# untitled.net
KiCad netlist of a schematic drawn in EAGLE
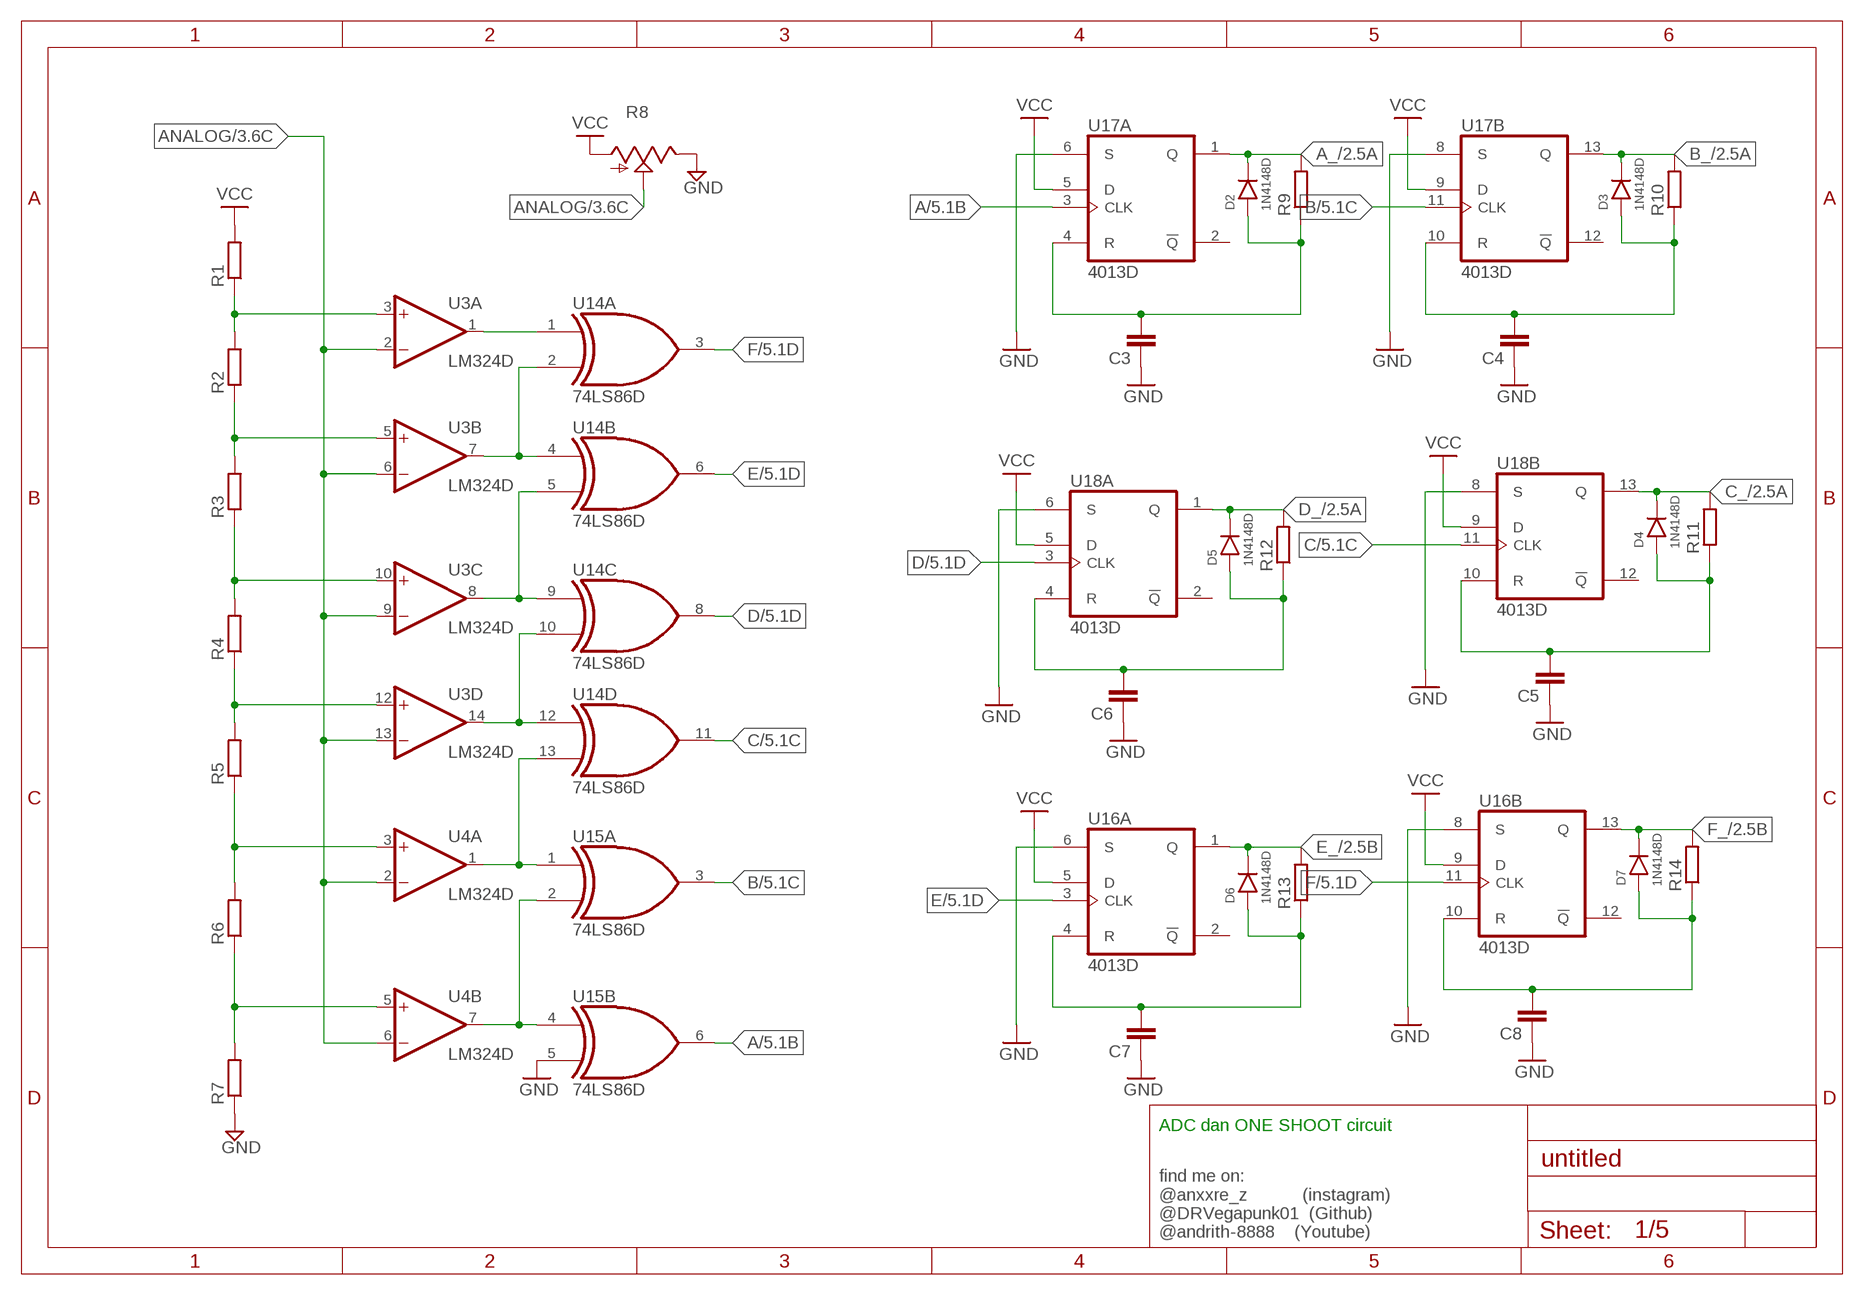
[diagram p0: schematic, sheet 1]
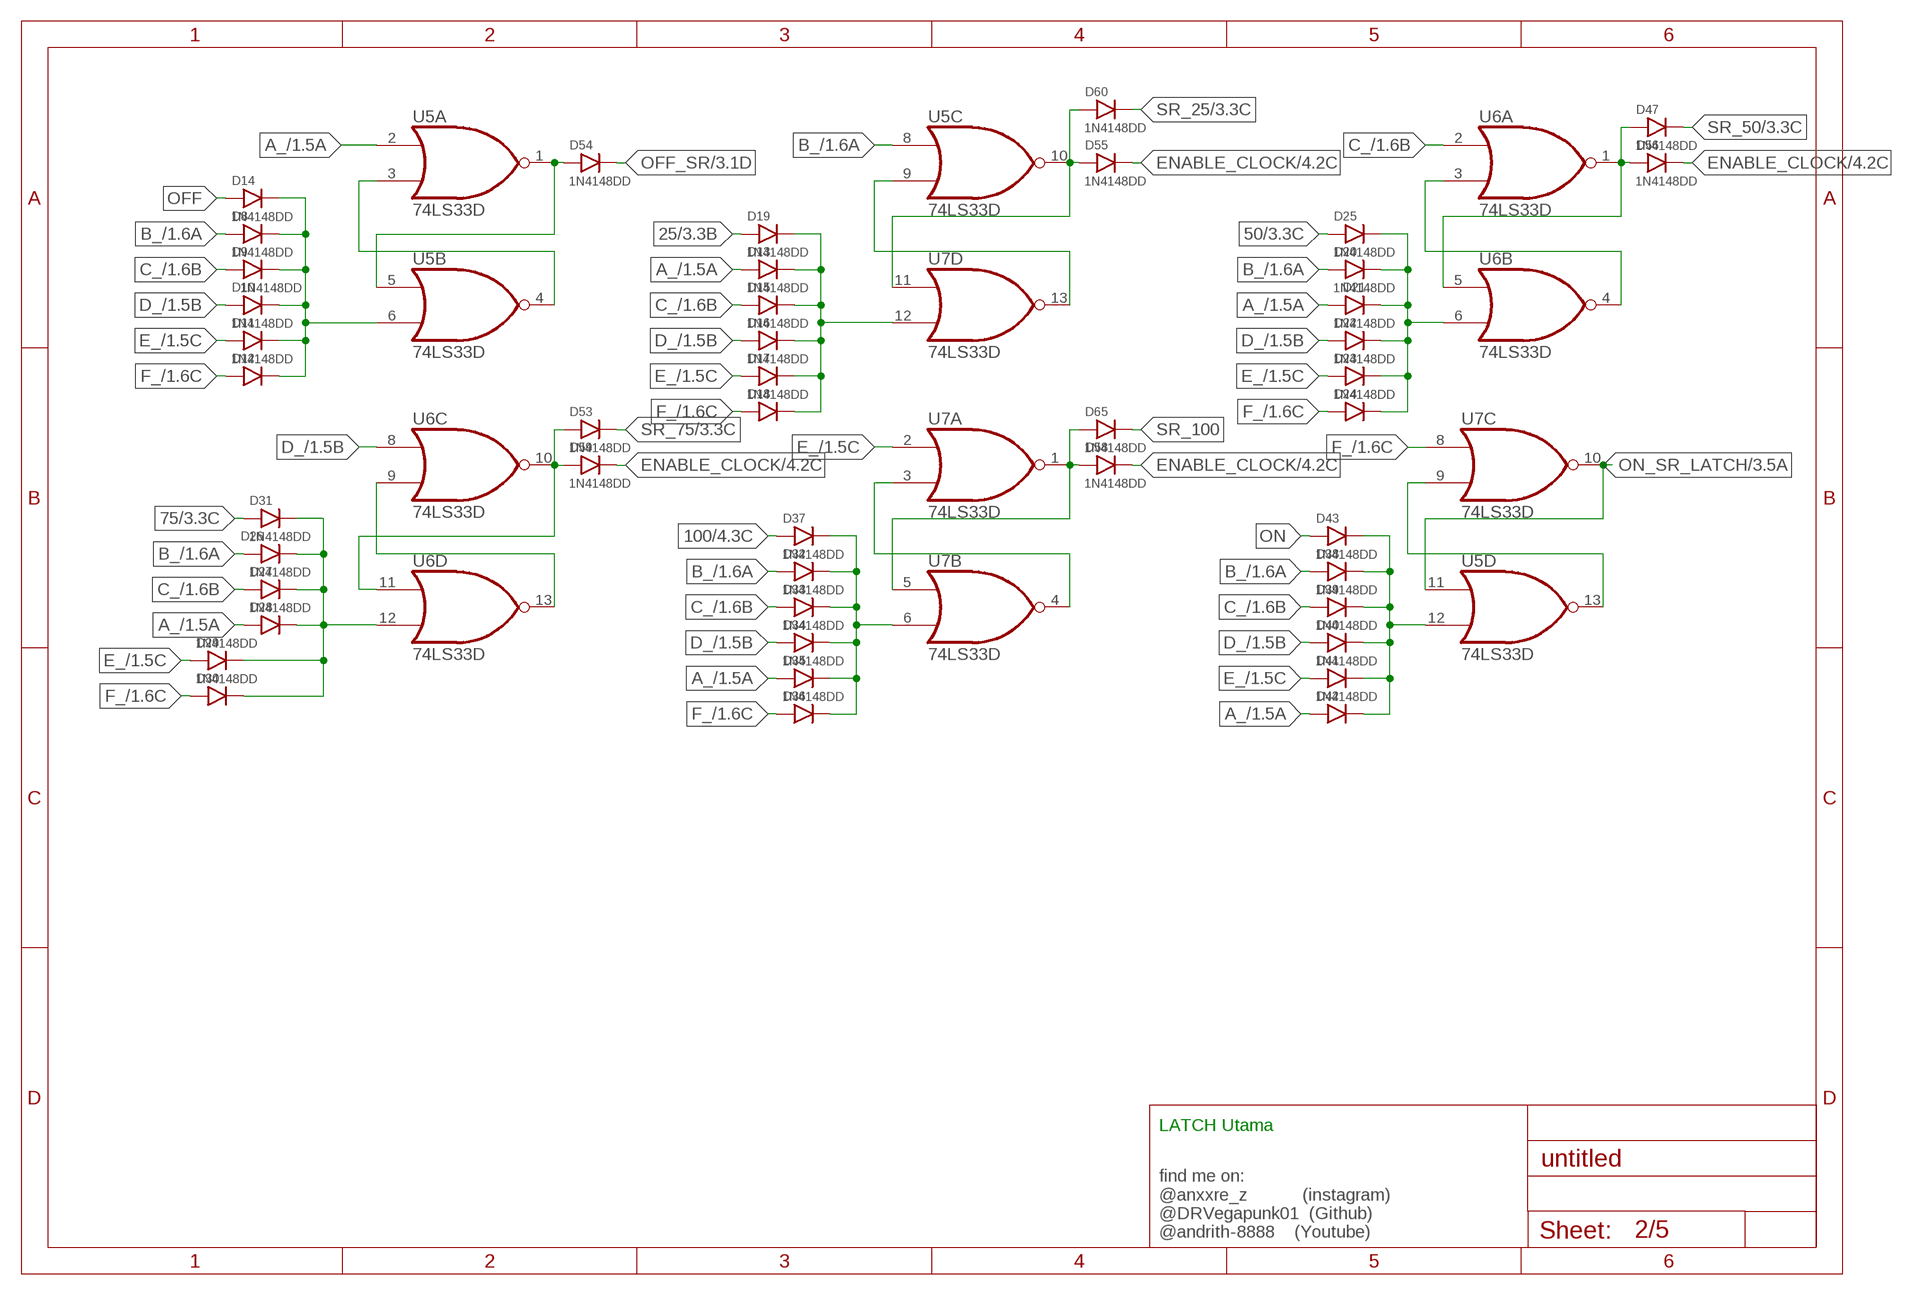
[diagram p1: schematic, sheet 2]
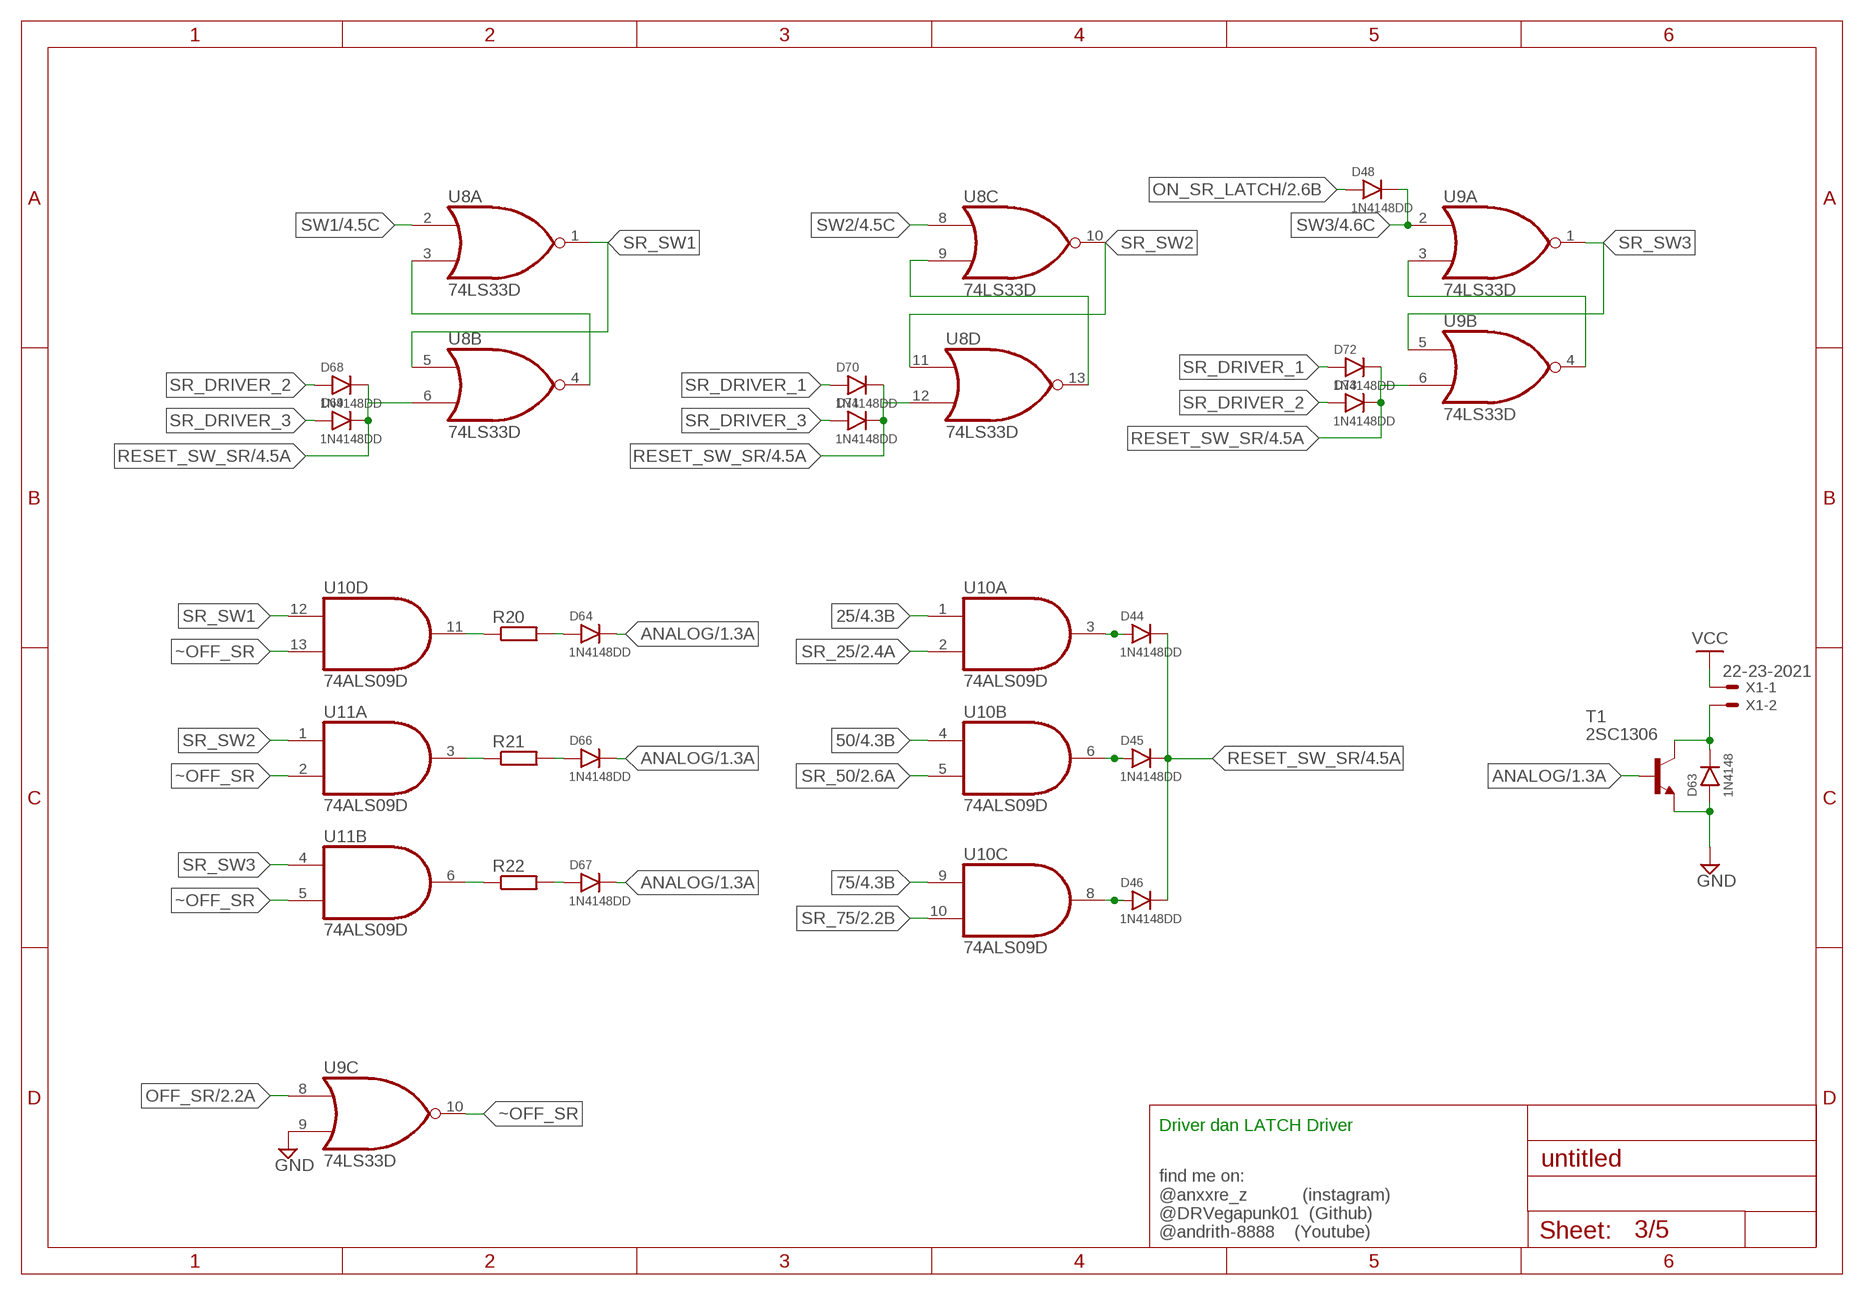
[diagram p2: schematic, sheet 3]
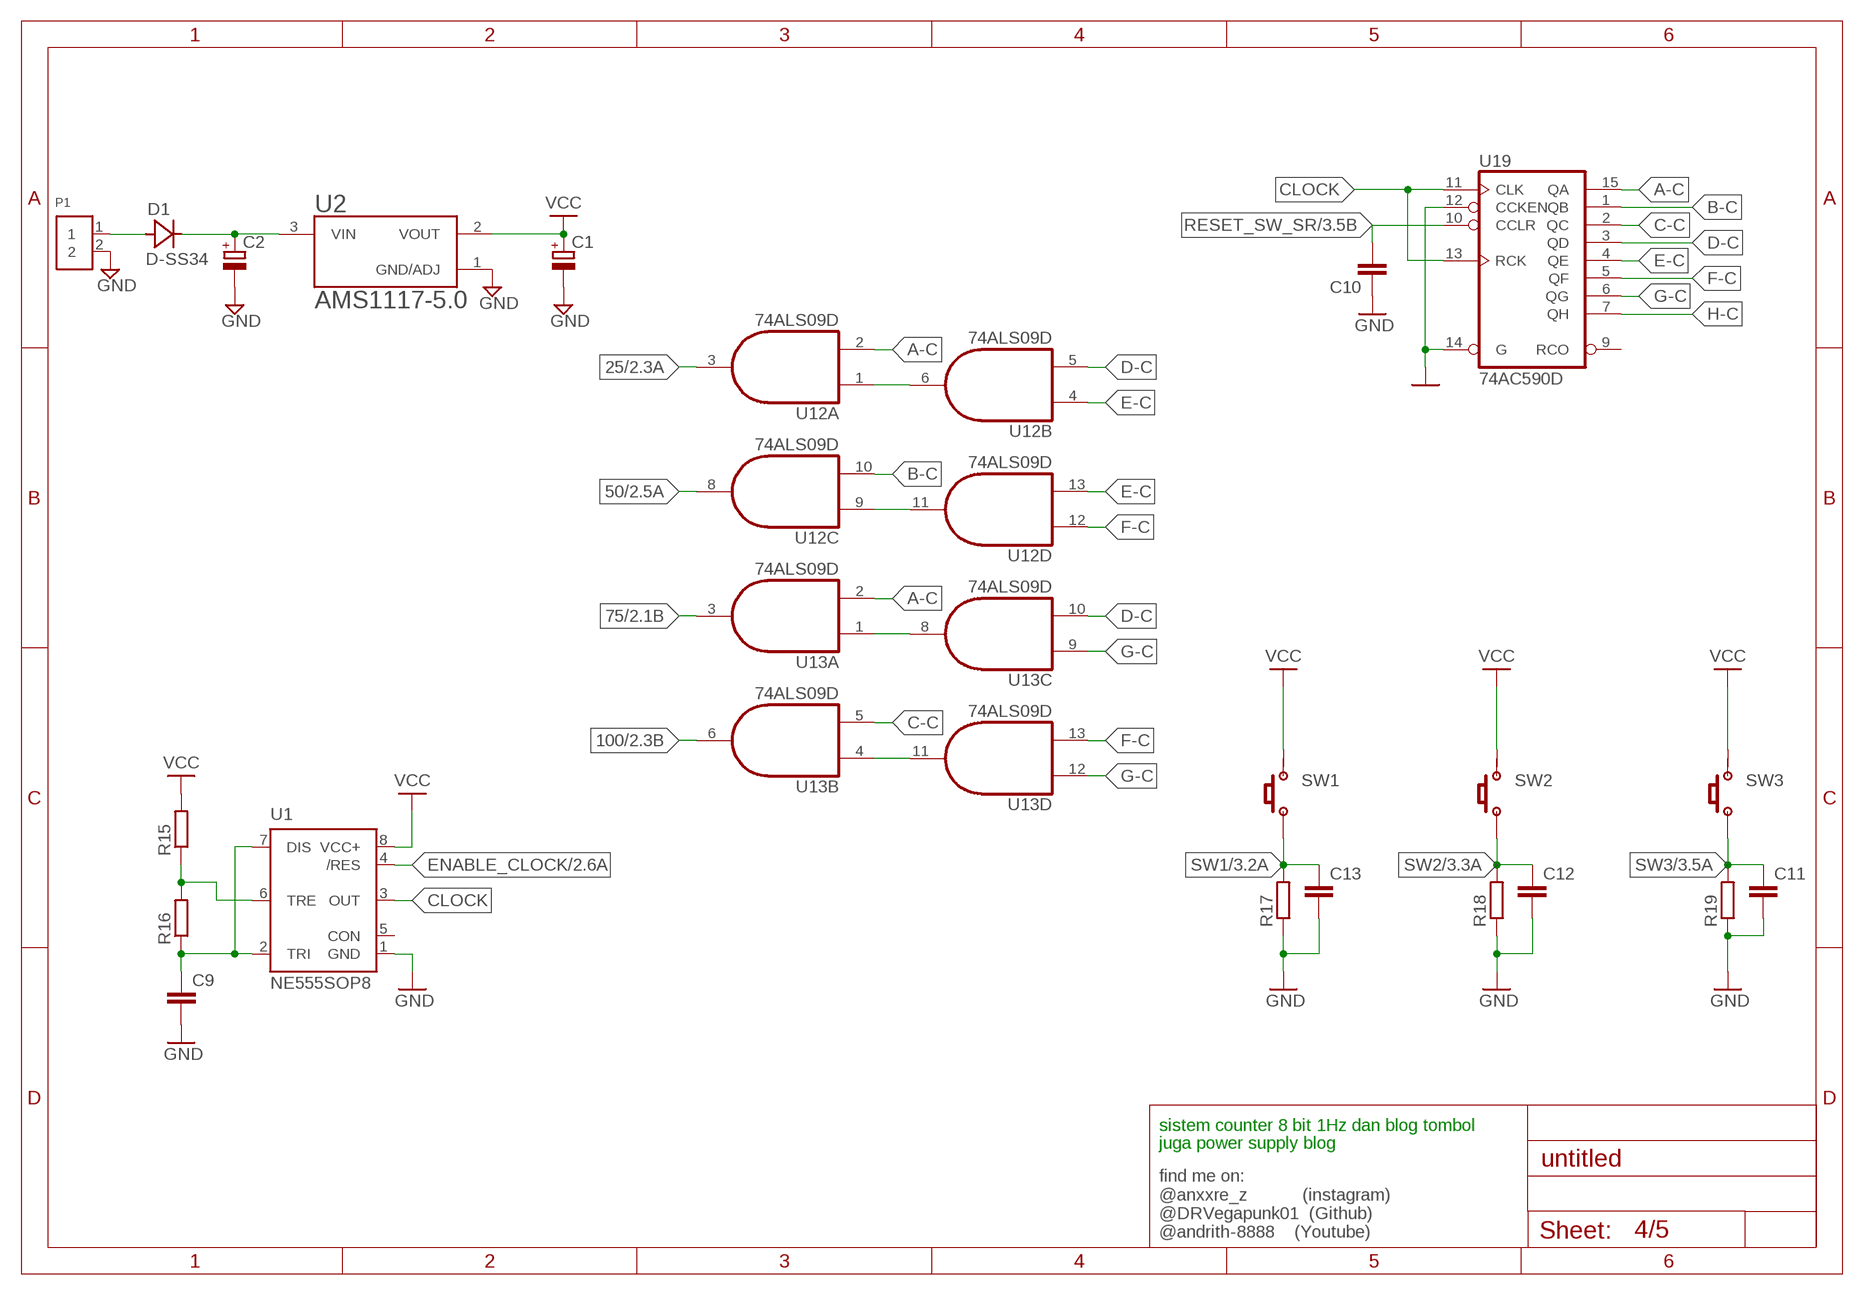
[diagram p3: schematic, sheet 4]
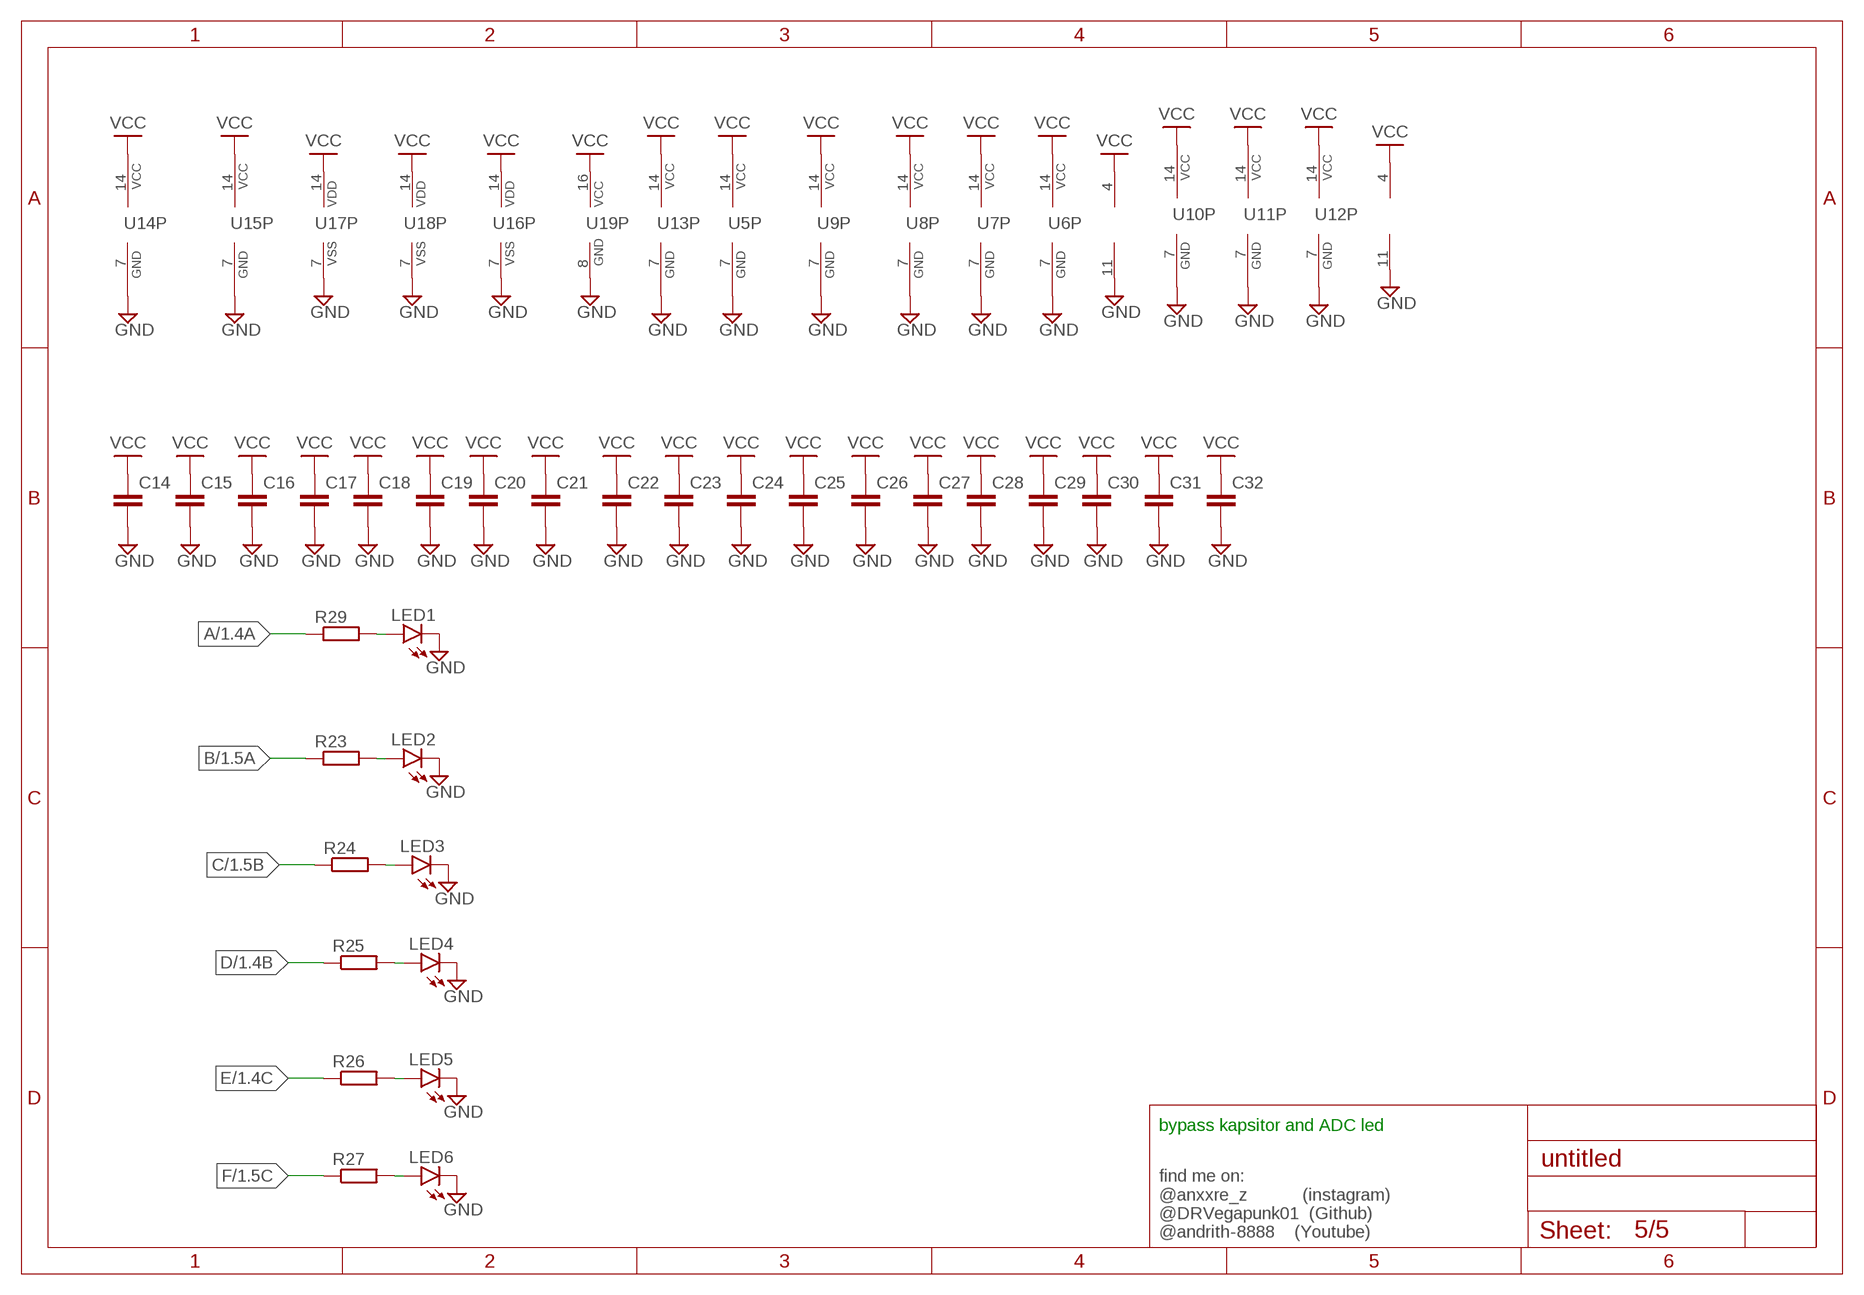
[diagram p4: schematic, sheet 5]

(export (version "E")
  (design (tool "Eeschema 10.0.6"))
  (components
    (comp (ref "D8")
      (value "1N4148DD")
      (footprint "eagle-import:SOD123")
      (libsource (lib "eagle-import") (part "1N4148DD"))
    )
    (comp (ref "D9")
      (value "1N4148DD")
      (footprint "eagle-import:SOD123")
      (libsource (lib "eagle-import") (part "1N4148DD"))
    )
    (comp (ref "D10")
      (value "1N4148DD")
      (footprint "eagle-import:SOD123")
      (libsource (lib "eagle-import") (part "1N4148DD"))
    )
    (comp (ref "D11")
      (value "1N4148DD")
      (footprint "eagle-import:SOD123")
      (libsource (lib "eagle-import") (part "1N4148DD"))
    )
    (comp (ref "D12")
      (value "1N4148DD")
      (footprint "eagle-import:SOD123")
      (libsource (lib "eagle-import") (part "1N4148DD"))
    )
    (comp (ref "D13")
      (value "1N4148DD")
      (footprint "eagle-import:SOD123")
      (libsource (lib "eagle-import") (part "1N4148DD"))
    )
    (comp (ref "D14")
      (value "1N4148DD")
      (footprint "eagle-import:SOD123")
      (libsource (lib "eagle-import") (part "1N4148DD"))
    )
    (comp (ref "D15")
      (value "1N4148DD")
      (footprint "eagle-import:SOD123")
      (libsource (lib "eagle-import") (part "1N4148DD"))
    )
    (comp (ref "D16")
      (value "1N4148DD")
      (footprint "eagle-import:SOD123")
      (libsource (lib "eagle-import") (part "1N4148DD"))
    )
    (comp (ref "D17")
      (value "1N4148DD")
      (footprint "eagle-import:SOD123")
      (libsource (lib "eagle-import") (part "1N4148DD"))
    )
    (comp (ref "D18")
      (value "1N4148DD")
      (footprint "eagle-import:SOD123")
      (libsource (lib "eagle-import") (part "1N4148DD"))
    )
    (comp (ref "D19")
      (value "1N4148DD")
      (footprint "eagle-import:SOD123")
      (libsource (lib "eagle-import") (part "1N4148DD"))
    )
    (comp (ref "D20")
      (value "1N4148DD")
      (footprint "eagle-import:SOD123")
      (libsource (lib "eagle-import") (part "1N4148DD"))
    )
    (comp (ref "D21")
      (value "1N4148DD")
      (footprint "eagle-import:SOD123")
      (libsource (lib "eagle-import") (part "1N4148DD"))
    )
    (comp (ref "D22")
      (value "1N4148DD")
      (footprint "eagle-import:SOD123")
      (libsource (lib "eagle-import") (part "1N4148DD"))
    )
    (comp (ref "D23")
      (value "1N4148DD")
      (footprint "eagle-import:SOD123")
      (libsource (lib "eagle-import") (part "1N4148DD"))
    )
    (comp (ref "D24")
      (value "1N4148DD")
      (footprint "eagle-import:SOD123")
      (libsource (lib "eagle-import") (part "1N4148DD"))
    )
    (comp (ref "D25")
      (value "1N4148DD")
      (footprint "eagle-import:SOD123")
      (libsource (lib "eagle-import") (part "1N4148DD"))
    )
    (comp (ref "D26")
      (value "1N4148DD")
      (footprint "eagle-import:SOD123")
      (libsource (lib "eagle-import") (part "1N4148DD"))
    )
    (comp (ref "D27")
      (value "1N4148DD")
      (footprint "eagle-import:SOD123")
      (libsource (lib "eagle-import") (part "1N4148DD"))
    )
    (comp (ref "D28")
      (value "1N4148DD")
      (footprint "eagle-import:SOD123")
      (libsource (lib "eagle-import") (part "1N4148DD"))
    )
    (comp (ref "D29")
      (value "1N4148DD")
      (footprint "eagle-import:SOD123")
      (libsource (lib "eagle-import") (part "1N4148DD"))
    )
    (comp (ref "D30")
      (value "1N4148DD")
      (footprint "eagle-import:SOD123")
      (libsource (lib "eagle-import") (part "1N4148DD"))
    )
    (comp (ref "D31")
      (value "1N4148DD")
      (footprint "eagle-import:SOD123")
      (libsource (lib "eagle-import") (part "1N4148DD"))
    )
    (comp (ref "D32")
      (value "1N4148DD")
      (footprint "eagle-import:SOD123")
      (libsource (lib "eagle-import") (part "1N4148DD"))
    )
    (comp (ref "D33")
      (value "1N4148DD")
      (footprint "eagle-import:SOD123")
      (libsource (lib "eagle-import") (part "1N4148DD"))
    )
    (comp (ref "D34")
      (value "1N4148DD")
      (footprint "eagle-import:SOD123")
      (libsource (lib "eagle-import") (part "1N4148DD"))
    )
    (comp (ref "D35")
      (value "1N4148DD")
      (footprint "eagle-import:SOD123")
      (libsource (lib "eagle-import") (part "1N4148DD"))
    )
    (comp (ref "D36")
      (value "1N4148DD")
      (footprint "eagle-import:SOD123")
      (libsource (lib "eagle-import") (part "1N4148DD"))
    )
    (comp (ref "D37")
      (value "1N4148DD")
      (footprint "eagle-import:SOD123")
      (libsource (lib "eagle-import") (part "1N4148DD"))
    )
    (comp (ref "D38")
      (value "1N4148DD")
      (footprint "eagle-import:SOD123")
      (libsource (lib "eagle-import") (part "1N4148DD"))
    )
    (comp (ref "D39")
      (value "1N4148DD")
      (footprint "eagle-import:SOD123")
      (libsource (lib "eagle-import") (part "1N4148DD"))
    )
    (comp (ref "D40")
      (value "1N4148DD")
      (footprint "eagle-import:SOD123")
      (libsource (lib "eagle-import") (part "1N4148DD"))
    )
    (comp (ref "D41")
      (value "1N4148DD")
      (footprint "eagle-import:SOD123")
      (libsource (lib "eagle-import") (part "1N4148DD"))
    )
    (comp (ref "D42")
      (value "1N4148DD")
      (footprint "eagle-import:SOD123")
      (libsource (lib "eagle-import") (part "1N4148DD"))
    )
    (comp (ref "D43")
      (value "1N4148DD")
      (footprint "eagle-import:SOD123")
      (libsource (lib "eagle-import") (part "1N4148DD"))
    )
    (comp (ref "D47")
      (value "1N4148DD")
      (footprint "eagle-import:SOD123")
      (libsource (lib "eagle-import") (part "1N4148DD"))
    )
    (comp (ref "D53")
      (value "1N4148DD")
      (footprint "eagle-import:SOD123")
      (libsource (lib "eagle-import") (part "1N4148DD"))
    )
    (comp (ref "D54")
      (value "1N4148DD")
      (footprint "eagle-import:SOD123")
      (libsource (lib "eagle-import") (part "1N4148DD"))
    )
    (comp (ref "D55")
      (value "1N4148DD")
      (footprint "eagle-import:SOD123")
      (libsource (lib "eagle-import") (part "1N4148DD"))
    )
    (comp (ref "D56")
      (value "1N4148DD")
      (footprint "eagle-import:SOD123")
      (libsource (lib "eagle-import") (part "1N4148DD"))
    )
    (comp (ref "D58")
      (value "1N4148DD")
      (footprint "eagle-import:SOD123")
      (libsource (lib "eagle-import") (part "1N4148DD"))
    )
    (comp (ref "D59")
      (value "1N4148DD")
      (footprint "eagle-import:SOD123")
      (libsource (lib "eagle-import") (part "1N4148DD"))
    )
    (comp (ref "D60")
      (value "1N4148DD")
      (footprint "eagle-import:SOD123")
      (libsource (lib "eagle-import") (part "1N4148DD"))
    )
    (comp (ref "D65")
      (value "1N4148DD")
      (footprint "eagle-import:SOD123")
      (libsource (lib "eagle-import") (part "1N4148DD"))
    )
    (comp (ref "U5")
      (value "74LS33D")
      (footprint "eagle-import:SO14")
      (libsource (lib "eagle-import") (part "7433DLS"))
    )
    (comp (ref "U6")
      (value "74LS33D")
      (footprint "eagle-import:SO14")
      (libsource (lib "eagle-import") (part "7433DLS"))
    )
    (comp (ref "U7")
      (value "74LS33D")
      (footprint "eagle-import:SO14")
      (libsource (lib "eagle-import") (part "7433DLS"))
    )
    (comp (ref "D44")
      (value "1N4148DD")
      (footprint "eagle-import:SOD123")
      (libsource (lib "eagle-import") (part "1N4148DD"))
    )
    (comp (ref "D45")
      (value "1N4148DD")
      (footprint "eagle-import:SOD123")
      (libsource (lib "eagle-import") (part "1N4148DD"))
    )
    (comp (ref "D46")
      (value "1N4148DD")
      (footprint "eagle-import:SOD123")
      (libsource (lib "eagle-import") (part "1N4148DD"))
    )
    (comp (ref "D48")
      (value "1N4148DD")
      (footprint "eagle-import:SOD123")
      (libsource (lib "eagle-import") (part "1N4148DD"))
    )
    (comp (ref "D63")
      (value "1N4148")
      (footprint "eagle-import:DIODE")
      (libsource (lib "eagle-import") (part "1N4148"))
    )
    (comp (ref "D64")
      (value "1N4148DD")
      (footprint "eagle-import:SOD123")
      (libsource (lib "eagle-import") (part "1N4148DD"))
    )
    (comp (ref "D66")
      (value "1N4148DD")
      (footprint "eagle-import:SOD123")
      (libsource (lib "eagle-import") (part "1N4148DD"))
    )
    (comp (ref "D67")
      (value "1N4148DD")
      (footprint "eagle-import:SOD123")
      (libsource (lib "eagle-import") (part "1N4148DD"))
    )
    (comp (ref "D68")
      (value "1N4148DD")
      (footprint "eagle-import:SOD123")
      (libsource (lib "eagle-import") (part "1N4148DD"))
    )
    (comp (ref "D69")
      (value "1N4148DD")
      (footprint "eagle-import:SOD123")
      (libsource (lib "eagle-import") (part "1N4148DD"))
    )
    (comp (ref "D70")
      (value "1N4148DD")
      (footprint "eagle-import:SOD123")
      (libsource (lib "eagle-import") (part "1N4148DD"))
    )
    (comp (ref "D71")
      (value "1N4148DD")
      (footprint "eagle-import:SOD123")
      (libsource (lib "eagle-import") (part "1N4148DD"))
    )
    (comp (ref "D72")
      (value "1N4148DD")
      (footprint "eagle-import:SOD123")
      (libsource (lib "eagle-import") (part "1N4148DD"))
    )
    (comp (ref "D73")
      (value "1N4148DD")
      (footprint "eagle-import:SOD123")
      (libsource (lib "eagle-import") (part "1N4148DD"))
    )
    (comp (ref "R20")
      (value "RES0805")
      (footprint "eagle-import:SMD0805")
      (libsource (lib "eagle-import") (part "RES0805"))
    )
    (comp (ref "R21")
      (value "RES0805")
      (footprint "eagle-import:SMD0805")
      (libsource (lib "eagle-import") (part "RES0805"))
    )
    (comp (ref "R22")
      (value "RES0805")
      (footprint "eagle-import:SMD0805")
      (libsource (lib "eagle-import") (part "RES0805"))
    )
    (comp (ref "T1")
      (value "2SC1306")
      (footprint "eagle-import:TO220BV")
      (libsource (lib "eagle-import") (part "2SC1306"))
    )
    (comp (ref "U8")
      (value "74LS33D")
      (footprint "eagle-import:SO14")
      (libsource (lib "eagle-import") (part "7433DLS"))
    )
    (comp (ref "U9")
      (value "74LS33D")
      (footprint "eagle-import:SO14")
      (libsource (lib "eagle-import") (part "7433DLS"))
    )
    (comp (ref "U10")
      (value "74ALS09D")
      (footprint "eagle-import:SO14")
      (libsource (lib "eagle-import") (part "7409DALS"))
    )
    (comp (ref "U11")
      (value "74ALS09D")
      (footprint "eagle-import:SO14")
      (libsource (lib "eagle-import") (part "7409DALS"))
    )
    (comp (ref "X1")
      (value "22-23-2021")
      (footprint "eagle-import:22-23-2021")
      (fields (field (name "MF") "MOLEX"))
      (libsource (lib "eagle-import") (part "22-23-2021"))
    )
    (comp (ref "C14")
      (value "CAP-NON0805")
      (footprint "eagle-import:SMD0805")
      (libsource (lib "eagle-import") (part "CAP-NON0805"))
    )
    (comp (ref "C15")
      (value "CAP-NON0805")
      (footprint "eagle-import:SMD0805")
      (libsource (lib "eagle-import") (part "CAP-NON0805"))
    )
    (comp (ref "C16")
      (value "CAP-NON0805")
      (footprint "eagle-import:SMD0805")
      (libsource (lib "eagle-import") (part "CAP-NON0805"))
    )
    (comp (ref "C17")
      (value "CAP-NON0805")
      (footprint "eagle-import:SMD0805")
      (libsource (lib "eagle-import") (part "CAP-NON0805"))
    )
    (comp (ref "C18")
      (value "CAP-NON0805")
      (footprint "eagle-import:SMD0805")
      (libsource (lib "eagle-import") (part "CAP-NON0805"))
    )
    (comp (ref "C19")
      (value "CAP-NON0805")
      (footprint "eagle-import:SMD0805")
      (libsource (lib "eagle-import") (part "CAP-NON0805"))
    )
    (comp (ref "C20")
      (value "CAP-NON0805")
      (footprint "eagle-import:SMD0805")
      (libsource (lib "eagle-import") (part "CAP-NON0805"))
    )
    (comp (ref "C21")
      (value "CAP-NON0805")
      (footprint "eagle-import:SMD0805")
      (libsource (lib "eagle-import") (part "CAP-NON0805"))
    )
    (comp (ref "C22")
      (value "CAP-NON0805")
      (footprint "eagle-import:SMD0805")
      (libsource (lib "eagle-import") (part "CAP-NON0805"))
    )
    (comp (ref "C23")
      (value "CAP-NON0805")
      (footprint "eagle-import:SMD0805")
      (libsource (lib "eagle-import") (part "CAP-NON0805"))
    )
    (comp (ref "C24")
      (value "CAP-NON0805")
      (footprint "eagle-import:SMD0805")
      (libsource (lib "eagle-import") (part "CAP-NON0805"))
    )
    (comp (ref "C25")
      (value "CAP-NON0805")
      (footprint "eagle-import:SMD0805")
      (libsource (lib "eagle-import") (part "CAP-NON0805"))
    )
    (comp (ref "C26")
      (value "CAP-NON0805")
      (footprint "eagle-import:SMD0805")
      (libsource (lib "eagle-import") (part "CAP-NON0805"))
    )
    (comp (ref "C27")
      (value "CAP-NON0805")
      (footprint "eagle-import:SMD0805")
      (libsource (lib "eagle-import") (part "CAP-NON0805"))
    )
    (comp (ref "C28")
      (value "CAP-NON0805")
      (footprint "eagle-import:SMD0805")
      (libsource (lib "eagle-import") (part "CAP-NON0805"))
    )
    (comp (ref "C29")
      (value "CAP-NON0805")
      (footprint "eagle-import:SMD0805")
      (libsource (lib "eagle-import") (part "CAP-NON0805"))
    )
    (comp (ref "C30")
      (value "CAP-NON0805")
      (footprint "eagle-import:SMD0805")
      (libsource (lib "eagle-import") (part "CAP-NON0805"))
    )
    (comp (ref "C31")
      (value "CAP-NON0805")
      (footprint "eagle-import:SMD0805")
      (libsource (lib "eagle-import") (part "CAP-NON0805"))
    )
    (comp (ref "C32")
      (value "CAP-NON0805")
      (footprint "eagle-import:SMD0805")
      (libsource (lib "eagle-import") (part "CAP-NON0805"))
    )
    (comp (ref "LED1")
      (value "LED0805")
      (footprint "eagle-import:CHIPLED_0805")
      (libsource (lib "eagle-import") (part "LED0805"))
    )
    (comp (ref "LED2")
      (value "LED0805")
      (footprint "eagle-import:CHIPLED_0805")
      (libsource (lib "eagle-import") (part "LED0805"))
    )
    (comp (ref "LED3")
      (value "LED0805")
      (footprint "eagle-import:CHIPLED_0805")
      (libsource (lib "eagle-import") (part "LED0805"))
    )
    (comp (ref "LED4")
      (value "LED0805")
      (footprint "eagle-import:CHIPLED_0805")
      (libsource (lib "eagle-import") (part "LED0805"))
    )
    (comp (ref "LED5")
      (value "LED0805")
      (footprint "eagle-import:CHIPLED_0805")
      (libsource (lib "eagle-import") (part "LED0805"))
    )
    (comp (ref "LED6")
      (value "LED0805")
      (footprint "eagle-import:CHIPLED_0805")
      (libsource (lib "eagle-import") (part "LED0805"))
    )
    (comp (ref "R23")
      (value "RES0805")
      (footprint "eagle-import:SMD0805")
      (libsource (lib "eagle-import") (part "RES0805"))
    )
    (comp (ref "R24")
      (value "RES0805")
      (footprint "eagle-import:SMD0805")
      (libsource (lib "eagle-import") (part "RES0805"))
    )
    (comp (ref "R25")
      (value "RES0805")
      (footprint "eagle-import:SMD0805")
      (libsource (lib "eagle-import") (part "RES0805"))
    )
    (comp (ref "R26")
      (value "RES0805")
      (footprint "eagle-import:SMD0805")
      (libsource (lib "eagle-import") (part "RES0805"))
    )
    (comp (ref "R27")
      (value "RES0805")
      (footprint "eagle-import:SMD0805")
      (libsource (lib "eagle-import") (part "RES0805"))
    )
    (comp (ref "R29")
      (value "RES0805")
      (footprint "eagle-import:SMD0805")
      (libsource (lib "eagle-import") (part "RES0805"))
    )
    (comp (ref "U3")
      (value "LM324D")
      (footprint "eagle-import:SO14")
      (libsource (lib "eagle-import") (part "LM324D"))
    )
    (comp (ref "U4")
      (value "LM324D")
      (footprint "eagle-import:SO14")
      (libsource (lib "eagle-import") (part "LM324D"))
    )
    (comp (ref "U12")
      (value "74ALS09D")
      (footprint "eagle-import:SO14")
      (libsource (lib "eagle-import") (part "7409DALS"))
    )
    (comp (ref "U13")
      (value "74ALS09D")
      (footprint "eagle-import:SO14")
      (libsource (lib "eagle-import") (part "7409DALS"))
    )
    (comp (ref "U14")
      (value "74LS86D")
      (footprint "eagle-import:SO14")
      (libsource (lib "eagle-import") (part "7486DLS"))
    )
    (comp (ref "U15")
      (value "74LS86D")
      (footprint "eagle-import:SO14")
      (libsource (lib "eagle-import") (part "7486DLS"))
    )
    (comp (ref "U16")
      (value "4013D")
      (footprint "eagle-import:SO14")
      (libsource (lib "eagle-import") (part "4013D"))
    )
    (comp (ref "U17")
      (value "4013D")
      (footprint "eagle-import:SO14")
      (libsource (lib "eagle-import") (part "4013D"))
    )
    (comp (ref "U18")
      (value "4013D")
      (footprint "eagle-import:SO14")
      (libsource (lib "eagle-import") (part "4013D"))
    )
    (comp (ref "U19")
      (value "74AC590D")
      (footprint "eagle-import:SO16")
      (libsource (lib "eagle-import") (part "74590DAC"))
    )
    (comp (ref "C1")
      (value "CAP-POLARE5-4")
      (footprint "eagle-import:E5-4")
      (libsource (lib "eagle-import") (part "CAP-POLARE5-4"))
    )
    (comp (ref "C2")
      (value "CAP-POLARE5-4")
      (footprint "eagle-import:E5-4")
      (libsource (lib "eagle-import") (part "CAP-POLARE5-4"))
    )
    (comp (ref "C9")
      (value "CAP-NON0805")
      (footprint "eagle-import:SMD0805")
      (libsource (lib "eagle-import") (part "CAP-NON0805"))
    )
    (comp (ref "C10")
      (value "CAP-NON0805")
      (footprint "eagle-import:SMD0805")
      (libsource (lib "eagle-import") (part "CAP-NON0805"))
    )
    (comp (ref "C11")
      (value "CAP-NON0805")
      (footprint "eagle-import:SMD0805")
      (libsource (lib "eagle-import") (part "CAP-NON0805"))
    )
    (comp (ref "C12")
      (value "CAP-NON0805")
      (footprint "eagle-import:SMD0805")
      (libsource (lib "eagle-import") (part "CAP-NON0805"))
    )
    (comp (ref "C13")
      (value "CAP-NON0805")
      (footprint "eagle-import:SMD0805")
      (libsource (lib "eagle-import") (part "CAP-NON0805"))
    )
    (comp (ref "D1")
      (value "D-SS34")
      (footprint "eagle-import:SMA")
      (libsource (lib "eagle-import") (part "D-SS34"))
    )
    (comp (ref "P1")
      (value "TERMINALBLOK")
      (footprint "eagle-import:TB-2P")
      (libsource (lib "eagle-import") (part "TERMINALBLOK"))
    )
    (comp (ref "R15")
      (value "RES0805")
      (footprint "eagle-import:SMD0805")
      (libsource (lib "eagle-import") (part "RES0805"))
    )
    (comp (ref "R16")
      (value "RES0805")
      (footprint "eagle-import:SMD0805")
      (libsource (lib "eagle-import") (part "RES0805"))
    )
    (comp (ref "R17")
      (value "RES0805")
      (footprint "eagle-import:SMD0805")
      (libsource (lib "eagle-import") (part "RES0805"))
    )
    (comp (ref "R18")
      (value "RES0805")
      (footprint "eagle-import:SMD0805")
      (libsource (lib "eagle-import") (part "RES0805"))
    )
    (comp (ref "R19")
      (value "RES0805")
      (footprint "eagle-import:SMD0805")
      (libsource (lib "eagle-import") (part "RES0805"))
    )
    (comp (ref "SW1")
      (value "PUSH_BUTTON4P")
      (footprint "eagle-import:PUSH_BUTTON_4P")
      (libsource (lib "eagle-import") (part "PUSH_BUTTON4P"))
    )
    (comp (ref "SW2")
      (value "PUSH_BUTTON4P")
      (footprint "eagle-import:PUSH_BUTTON_4P")
      (libsource (lib "eagle-import") (part "PUSH_BUTTON4P"))
    )
    (comp (ref "SW3")
      (value "PUSH_BUTTON4P")
      (footprint "eagle-import:PUSH_BUTTON_4P")
      (libsource (lib "eagle-import") (part "PUSH_BUTTON4P"))
    )
    (comp (ref "U1")
      (value "NE555SOP8")
      (footprint "eagle-import:SO08")
      (libsource (lib "eagle-import") (part "NE555SOP8"))
    )
    (comp (ref "U2")
      (value "AMS1117-5.0")
      (footprint "eagle-import:SOT229P700X180-4N")
      (libsource (lib "eagle-import") (part "AMS1117-5.0"))
    )
    (comp (ref "C3")
      (value "CAP-NON0805")
      (footprint "eagle-import:SMD0805")
      (libsource (lib "eagle-import") (part "CAP-NON0805"))
    )
    (comp (ref "C4")
      (value "CAP-NON0805")
      (footprint "eagle-import:SMD0805")
      (libsource (lib "eagle-import") (part "CAP-NON0805"))
    )
    (comp (ref "C5")
      (value "CAP-NON0805")
      (footprint "eagle-import:SMD0805")
      (libsource (lib "eagle-import") (part "CAP-NON0805"))
    )
    (comp (ref "C6")
      (value "CAP-NON0805")
      (footprint "eagle-import:SMD0805")
      (libsource (lib "eagle-import") (part "CAP-NON0805"))
    )
    (comp (ref "C7")
      (value "CAP-NON0805")
      (footprint "eagle-import:SMD0805")
      (libsource (lib "eagle-import") (part "CAP-NON0805"))
    )
    (comp (ref "C8")
      (value "CAP-NON0805")
      (footprint "eagle-import:SMD0805")
      (libsource (lib "eagle-import") (part "CAP-NON0805"))
    )
    (comp (ref "D2")
      (value "1N4148D")
      (footprint "eagle-import:SOD80C")
      (libsource (lib "eagle-import") (part "1N4148D"))
    )
    (comp (ref "D3")
      (value "1N4148D")
      (footprint "eagle-import:SOD80C")
      (libsource (lib "eagle-import") (part "1N4148D"))
    )
    (comp (ref "D4")
      (value "1N4148D")
      (footprint "eagle-import:SOD80C")
      (libsource (lib "eagle-import") (part "1N4148D"))
    )
    (comp (ref "D5")
      (value "1N4148D")
      (footprint "eagle-import:SOD80C")
      (libsource (lib "eagle-import") (part "1N4148D"))
    )
    (comp (ref "D6")
      (value "1N4148D")
      (footprint "eagle-import:SOD80C")
      (libsource (lib "eagle-import") (part "1N4148D"))
    )
    (comp (ref "D7")
      (value "1N4148D")
      (footprint "eagle-import:SOD80C")
      (libsource (lib "eagle-import") (part "1N4148D"))
    )
    (comp (ref "R1")
      (value "RES0805")
      (footprint "eagle-import:SMD0805")
      (libsource (lib "eagle-import") (part "RES0805"))
    )
    (comp (ref "R2")
      (value "RES0805")
      (footprint "eagle-import:SMD0805")
      (libsource (lib "eagle-import") (part "RES0805"))
    )
    (comp (ref "R3")
      (value "RES0805")
      (footprint "eagle-import:SMD0805")
      (libsource (lib "eagle-import") (part "RES0805"))
    )
    (comp (ref "R4")
      (value "RES0805")
      (footprint "eagle-import:SMD0805")
      (libsource (lib "eagle-import") (part "RES0805"))
    )
    (comp (ref "R5")
      (value "RES0805")
      (footprint "eagle-import:SMD0805")
      (libsource (lib "eagle-import") (part "RES0805"))
    )
    (comp (ref "R6")
      (value "RES0805")
      (footprint "eagle-import:SMD0805")
      (libsource (lib "eagle-import") (part "RES0805"))
    )
    (comp (ref "R7")
      (value "RES0805")
      (footprint "eagle-import:SMD0805")
      (libsource (lib "eagle-import") (part "RES0805"))
    )
    (comp (ref "R8")
      (value "TRIM_US-CT6")
      (footprint "eagle-import:CT6")
      (libsource (lib "eagle-import") (part "TRIM_US-CT6"))
    )
    (comp (ref "R9")
      (value "RES0805")
      (footprint "eagle-import:SMD0805")
      (libsource (lib "eagle-import") (part "RES0805"))
    )
    (comp (ref "R10")
      (value "RES0805")
      (footprint "eagle-import:SMD0805")
      (libsource (lib "eagle-import") (part "RES0805"))
    )
    (comp (ref "R11")
      (value "RES0805")
      (footprint "eagle-import:SMD0805")
      (libsource (lib "eagle-import") (part "RES0805"))
    )
    (comp (ref "R12")
      (value "RES0805")
      (footprint "eagle-import:SMD0805")
      (libsource (lib "eagle-import") (part "RES0805"))
    )
    (comp (ref "R13")
      (value "RES0805")
      (footprint "eagle-import:SMD0805")
      (libsource (lib "eagle-import") (part "RES0805"))
    )
    (comp (ref "R14")
      (value "RES0805")
      (footprint "eagle-import:SMD0805")
      (libsource (lib "eagle-import") (part "RES0805"))
    )
  )
  (nets
    (net (code "1") (name "25") (class "Default")
      (node (ref "D19") (pin "A") (pinfunction "1_A") (pintype "bidirectional"))
      (node (ref "U10") (pin "1") (pinfunction "I0_1") (pintype "input"))
      (node (ref "U12") (pin "3") (pinfunction "O_3") (pintype "open_collector"))
    )
    (net (code "2") (name "50") (class "Default")
      (node (ref "D25") (pin "A") (pinfunction "1_A") (pintype "bidirectional"))
      (node (ref "U10") (pin "4") (pinfunction "I0_4") (pintype "input"))
      (node (ref "U12") (pin "8") (pinfunction "O_8") (pintype "open_collector"))
    )
    (net (code "3") (name "75") (class "Default")
      (node (ref "D31") (pin "A") (pinfunction "1_A") (pintype "bidirectional"))
      (node (ref "U10") (pin "9") (pinfunction "I0_9") (pintype "input"))
      (node (ref "U13") (pin "3") (pinfunction "O_3") (pintype "open_collector"))
    )
    (net (code "4") (name "100") (class "Default")
      (node (ref "D37") (pin "A") (pinfunction "1_A") (pintype "bidirectional"))
      (node (ref "U13") (pin "6") (pinfunction "O_6") (pintype "open_collector"))
    )
    (net (code "5") (name "A") (class "Default")
      (node (ref "R29") (pin "1") (pinfunction "1_1") (pintype "passive"))
      (node (ref "U15") (pin "6") (pinfunction "O_6") (pintype "output"))
      (node (ref "U17") (pin "3") (pinfunction "CLK_3") (pintype "input"))
    )
    (net (code "6") (name "A-C") (class "Default")
      (node (ref "U12") (pin "2") (pinfunction "I1_2") (pintype "input"))
      (node (ref "U13") (pin "2") (pinfunction "I1_2") (pintype "input"))
      (node (ref "U19") (pin "15") (pinfunction "QA_15") (pintype "tri_state"))
    )
    (net (code "7") (name "ANALOG") (class "Default")
      (node (ref "D64") (pin "C") (pinfunction "2_C") (pintype "bidirectional"))
      (node (ref "D66") (pin "C") (pinfunction "2_C") (pintype "bidirectional"))
      (node (ref "D67") (pin "C") (pinfunction "2_C") (pintype "bidirectional"))
      (node (ref "R8") (pin "S") (pinfunction "S_S") (pintype "passive"))
      (node (ref "T1") (pin "1") (pinfunction "B_1") (pintype "passive"))
      (node (ref "U3") (pin "13") (pinfunction "-IN_13") (pintype "input"))
      (node (ref "U3") (pin "2") (pinfunction "-IN_2") (pintype "input"))
      (node (ref "U3") (pin "6") (pinfunction "-IN_6") (pintype "input"))
      (node (ref "U3") (pin "9") (pinfunction "-IN_9") (pintype "input"))
      (node (ref "U4") (pin "2") (pinfunction "-IN_2") (pintype "input"))
      (node (ref "U4") (pin "6") (pinfunction "-IN_6") (pintype "input"))
    )
    (net (code "8") (name "A_") (class "Default")
      (node (ref "D13") (pin "A") (pinfunction "1_A") (pintype "bidirectional"))
      (node (ref "D2") (pin "C") (pinfunction "2_C") (pintype "bidirectional"))
      (node (ref "D21") (pin "A") (pinfunction "1_A") (pintype "bidirectional"))
      (node (ref "D28") (pin "A") (pinfunction "1_A") (pintype "bidirectional"))
      (node (ref "D35") (pin "A") (pinfunction "1_A") (pintype "bidirectional"))
      (node (ref "D42") (pin "A") (pinfunction "1_A") (pintype "bidirectional"))
      (node (ref "R9") (pin "2") (pinfunction "2_2") (pintype "passive"))
      (node (ref "U17") (pin "1") (pinfunction "Q_1") (pintype "output"))
      (node (ref "U5") (pin "2") (pinfunction "I0_2") (pintype "input"))
    )
    (net (code "9") (name "B") (class "Default")
      (node (ref "R23") (pin "1") (pinfunction "1_1") (pintype "passive"))
      (node (ref "U15") (pin "3") (pinfunction "O_3") (pintype "output"))
      (node (ref "U17") (pin "11") (pinfunction "CLK_11") (pintype "input"))
    )
    (net (code "10") (name "B-C") (class "Default")
      (node (ref "U12") (pin "10") (pinfunction "I1_10") (pintype "input"))
      (node (ref "U19") (pin "1") (pinfunction "QB_1") (pintype "tri_state"))
    )
    (net (code "11") (name "B_") (class "Default")
      (node (ref "D20") (pin "A") (pinfunction "1_A") (pintype "bidirectional"))
      (node (ref "D26") (pin "A") (pinfunction "1_A") (pintype "bidirectional"))
      (node (ref "D3") (pin "C") (pinfunction "2_C") (pintype "bidirectional"))
      (node (ref "D32") (pin "A") (pinfunction "1_A") (pintype "bidirectional"))
      (node (ref "D38") (pin "A") (pinfunction "1_A") (pintype "bidirectional"))
      (node (ref "D8") (pin "A") (pinfunction "1_A") (pintype "bidirectional"))
      (node (ref "R10") (pin "2") (pinfunction "2_2") (pintype "passive"))
      (node (ref "U17") (pin "13") (pinfunction "Q_13") (pintype "output"))
      (node (ref "U5") (pin "8") (pinfunction "I0_8") (pintype "input"))
    )
    (net (code "12") (name "C") (class "Default")
      (node (ref "R24") (pin "1") (pinfunction "1_1") (pintype "passive"))
      (node (ref "U14") (pin "11") (pinfunction "O_11") (pintype "output"))
      (node (ref "U18") (pin "11") (pinfunction "CLK_11") (pintype "input"))
    )
    (net (code "13") (name "C-C") (class "Default")
      (node (ref "U13") (pin "5") (pinfunction "I1_5") (pintype "input"))
      (node (ref "U19") (pin "2") (pinfunction "QC_2") (pintype "tri_state"))
    )
    (net (code "14") (name "CLOCK") (class "Default")
      (node (ref "U1") (pin "3") (pinfunction "OUT_3") (pintype "output"))
      (node (ref "U19") (pin "11") (pinfunction "CLK_11") (pintype "input"))
      (node (ref "U19") (pin "13") (pinfunction "RCK_13") (pintype "input"))
    )
    (net (code "15") (name "C_") (class "Default")
      (node (ref "D15") (pin "A") (pinfunction "1_A") (pintype "bidirectional"))
      (node (ref "D27") (pin "A") (pinfunction "1_A") (pintype "bidirectional"))
      (node (ref "D33") (pin "A") (pinfunction "1_A") (pintype "bidirectional"))
      (node (ref "D39") (pin "A") (pinfunction "1_A") (pintype "bidirectional"))
      (node (ref "D4") (pin "C") (pinfunction "2_C") (pintype "bidirectional"))
      (node (ref "D9") (pin "A") (pinfunction "1_A") (pintype "bidirectional"))
      (node (ref "R11") (pin "2") (pinfunction "2_2") (pintype "passive"))
      (node (ref "U18") (pin "13") (pinfunction "Q_13") (pintype "output"))
      (node (ref "U6") (pin "2") (pinfunction "I0_2") (pintype "input"))
    )
    (net (code "16") (name "D") (class "Default")
      (node (ref "R25") (pin "1") (pinfunction "1_1") (pintype "passive"))
      (node (ref "U14") (pin "8") (pinfunction "O_8") (pintype "output"))
      (node (ref "U18") (pin "3") (pinfunction "CLK_3") (pintype "input"))
    )
    (net (code "17") (name "D-C") (class "Default")
      (node (ref "U12") (pin "5") (pinfunction "I1_5") (pintype "input"))
      (node (ref "U13") (pin "10") (pinfunction "I1_10") (pintype "input"))
      (node (ref "U19") (pin "3") (pinfunction "QD_3") (pintype "tri_state"))
    )
    (net (code "18") (name "D_") (class "Default")
      (node (ref "D10") (pin "A") (pinfunction "1_A") (pintype "bidirectional"))
      (node (ref "D16") (pin "A") (pinfunction "1_A") (pintype "bidirectional"))
      (node (ref "D22") (pin "A") (pinfunction "1_A") (pintype "bidirectional"))
      (node (ref "D34") (pin "A") (pinfunction "1_A") (pintype "bidirectional"))
      (node (ref "D40") (pin "A") (pinfunction "1_A") (pintype "bidirectional"))
      (node (ref "D5") (pin "C") (pinfunction "2_C") (pintype "bidirectional"))
      (node (ref "R12") (pin "2") (pinfunction "2_2") (pintype "passive"))
      (node (ref "U18") (pin "1") (pinfunction "Q_1") (pintype "output"))
      (node (ref "U6") (pin "8") (pinfunction "I0_8") (pintype "input"))
    )
    (net (code "19") (name "E") (class "Default")
      (node (ref "R26") (pin "1") (pinfunction "1_1") (pintype "passive"))
      (node (ref "U14") (pin "6") (pinfunction "O_6") (pintype "output"))
      (node (ref "U16") (pin "3") (pinfunction "CLK_3") (pintype "input"))
    )
    (net (code "20") (name "E-C") (class "Default")
      (node (ref "U12") (pin "13") (pinfunction "I1_13") (pintype "input"))
      (node (ref "U12") (pin "4") (pinfunction "I0_4") (pintype "input"))
      (node (ref "U19") (pin "4") (pinfunction "QE_4") (pintype "tri_state"))
    )
    (net (code "21") (name "ENABLE_CLOCK") (class "Default")
      (node (ref "D55") (pin "C") (pinfunction "2_C") (pintype "bidirectional"))
      (node (ref "D56") (pin "C") (pinfunction "2_C") (pintype "bidirectional"))
      (node (ref "D58") (pin "C") (pinfunction "2_C") (pintype "bidirectional"))
      (node (ref "D59") (pin "C") (pinfunction "2_C") (pintype "bidirectional"))
      (node (ref "U1") (pin "4") (pinfunction "/RES_4") (pintype "input"))
    )
    (net (code "22") (name "E_") (class "Default")
      (node (ref "D11") (pin "A") (pinfunction "1_A") (pintype "bidirectional"))
      (node (ref "D17") (pin "A") (pinfunction "1_A") (pintype "bidirectional"))
      (node (ref "D23") (pin "A") (pinfunction "1_A") (pintype "bidirectional"))
      (node (ref "D29") (pin "A") (pinfunction "1_A") (pintype "bidirectional"))
      (node (ref "D41") (pin "A") (pinfunction "1_A") (pintype "bidirectional"))
      (node (ref "D6") (pin "C") (pinfunction "2_C") (pintype "bidirectional"))
      (node (ref "R13") (pin "2") (pinfunction "2_2") (pintype "passive"))
      (node (ref "U16") (pin "1") (pinfunction "Q_1") (pintype "output"))
      (node (ref "U7") (pin "2") (pinfunction "I0_2") (pintype "input"))
    )
    (net (code "23") (name "F") (class "Default")
      (node (ref "R27") (pin "1") (pinfunction "1_1") (pintype "passive"))
      (node (ref "U14") (pin "3") (pinfunction "O_3") (pintype "output"))
      (node (ref "U16") (pin "11") (pinfunction "CLK_11") (pintype "input"))
    )
    (net (code "24") (name "F-C") (class "Default")
      (node (ref "U12") (pin "12") (pinfunction "I0_12") (pintype "input"))
      (node (ref "U13") (pin "13") (pinfunction "I1_13") (pintype "input"))
      (node (ref "U19") (pin "5") (pinfunction "QF_5") (pintype "tri_state"))
    )
    (net (code "25") (name "F_") (class "Default")
      (node (ref "D12") (pin "A") (pinfunction "1_A") (pintype "bidirectional"))
      (node (ref "D18") (pin "A") (pinfunction "1_A") (pintype "bidirectional"))
      (node (ref "D24") (pin "A") (pinfunction "1_A") (pintype "bidirectional"))
      (node (ref "D30") (pin "A") (pinfunction "1_A") (pintype "bidirectional"))
      (node (ref "D36") (pin "A") (pinfunction "1_A") (pintype "bidirectional"))
      (node (ref "D7") (pin "C") (pinfunction "2_C") (pintype "bidirectional"))
      (node (ref "R14") (pin "2") (pinfunction "2_2") (pintype "passive"))
      (node (ref "U16") (pin "13") (pinfunction "Q_13") (pintype "output"))
      (node (ref "U7") (pin "8") (pinfunction "I0_8") (pintype "input"))
    )
    (net (code "26") (name "G-C") (class "Default")
      (node (ref "U13") (pin "12") (pinfunction "I0_12") (pintype "input"))
      (node (ref "U13") (pin "9") (pinfunction "I0_9") (pintype "input"))
      (node (ref "U19") (pin "6") (pinfunction "QG_6") (pintype "tri_state"))
    )
    (net (code "27") (name "GND") (class "Default")
      (node (ref "C1") (pin "-") (pinfunction "-_-") (pintype "passive"))
      (node (ref "C10") (pin "2") (pinfunction "2_2") (pintype "passive"))
      (node (ref "C11") (pin "2") (pinfunction "2_2") (pintype "passive"))
      (node (ref "C12") (pin "2") (pinfunction "2_2") (pintype "passive"))
      (node (ref "C13") (pin "2") (pinfunction "2_2") (pintype "passive"))
      (node (ref "C14") (pin "2") (pinfunction "2_2") (pintype "passive"))
      (node (ref "C15") (pin "2") (pinfunction "2_2") (pintype "passive"))
      (node (ref "C16") (pin "2") (pinfunction "2_2") (pintype "passive"))
      (node (ref "C17") (pin "2") (pinfunction "2_2") (pintype "passive"))
      (node (ref "C18") (pin "2") (pinfunction "2_2") (pintype "passive"))
      (node (ref "C19") (pin "2") (pinfunction "2_2") (pintype "passive"))
      (node (ref "C2") (pin "-") (pinfunction "-_-") (pintype "passive"))
      (node (ref "C20") (pin "2") (pinfunction "2_2") (pintype "passive"))
      (node (ref "C21") (pin "2") (pinfunction "2_2") (pintype "passive"))
      (node (ref "C22") (pin "2") (pinfunction "2_2") (pintype "passive"))
      (node (ref "C23") (pin "2") (pinfunction "2_2") (pintype "passive"))
      (node (ref "C24") (pin "2") (pinfunction "2_2") (pintype "passive"))
      (node (ref "C25") (pin "2") (pinfunction "2_2") (pintype "passive"))
      (node (ref "C26") (pin "2") (pinfunction "2_2") (pintype "passive"))
      (node (ref "C27") (pin "2") (pinfunction "2_2") (pintype "passive"))
      (node (ref "C28") (pin "2") (pinfunction "2_2") (pintype "passive"))
      (node (ref "C29") (pin "2") (pinfunction "2_2") (pintype "passive"))
      (node (ref "C3") (pin "1") (pinfunction "1_1") (pintype "passive"))
      (node (ref "C30") (pin "2") (pinfunction "2_2") (pintype "passive"))
      (node (ref "C31") (pin "2") (pinfunction "2_2") (pintype "passive"))
      (node (ref "C32") (pin "2") (pinfunction "2_2") (pintype "passive"))
      (node (ref "C4") (pin "1") (pinfunction "1_1") (pintype "passive"))
      (node (ref "C5") (pin "1") (pinfunction "1_1") (pintype "passive"))
      (node (ref "C6") (pin "1") (pinfunction "1_1") (pintype "passive"))
      (node (ref "C7") (pin "1") (pinfunction "1_1") (pintype "passive"))
      (node (ref "C8") (pin "1") (pinfunction "1_1") (pintype "passive"))
      (node (ref "C9") (pin "2") (pinfunction "2_2") (pintype "passive"))
      (node (ref "D63") (pin "1") (pinfunction "1_1") (pintype "bidirectional"))
      (node (ref "LED1") (pin "C") (pinfunction "C_C") (pintype "passive"))
      (node (ref "LED2") (pin "C") (pinfunction "C_C") (pintype "passive"))
      (node (ref "LED3") (pin "C") (pinfunction "C_C") (pintype "passive"))
      (node (ref "LED4") (pin "C") (pinfunction "C_C") (pintype "passive"))
      (node (ref "LED5") (pin "C") (pinfunction "C_C") (pintype "passive"))
      (node (ref "LED6") (pin "C") (pinfunction "C_C") (pintype "passive"))
      (node (ref "P1") (pin "2") (pinfunction "2_2") (pintype "bidirectional"))
      (node (ref "R17") (pin "1") (pinfunction "1_1") (pintype "passive"))
      (node (ref "R18") (pin "1") (pinfunction "1_1") (pintype "passive"))
      (node (ref "R19") (pin "1") (pinfunction "1_1") (pintype "passive"))
      (node (ref "R7") (pin "1") (pinfunction "1_1") (pintype "passive"))
      (node (ref "R8") (pin "E") (pinfunction "E_E") (pintype "passive"))
      (node (ref "T1") (pin "3") (pinfunction "E_3") (pintype "passive"))
      (node (ref "U1") (pin "1") (pinfunction "GND_1") (pintype "power_in"))
      (node (ref "U10") (pin "7") (pinfunction "GND_7") (pintype "power_in"))
      (node (ref "U11") (pin "7") (pinfunction "GND_7") (pintype "power_in"))
      (node (ref "U12") (pin "7") (pinfunction "GND_7") (pintype "power_in"))
      (node (ref "U13") (pin "7") (pinfunction "GND_7") (pintype "power_in"))
      (node (ref "U14") (pin "7") (pinfunction "GND_7") (pintype "power_in"))
      (node (ref "U15") (pin "5") (pinfunction "I1_5") (pintype "input"))
      (node (ref "U15") (pin "7") (pinfunction "GND_7") (pintype "power_in"))
      (node (ref "U16") (pin "6") (pinfunction "S_6") (pintype "input"))
      (node (ref "U16") (pin "7") (pinfunction "VSS_7") (pintype "power_in"))
      (node (ref "U16") (pin "8") (pinfunction "S_8") (pintype "input"))
      (node (ref "U17") (pin "6") (pinfunction "S_6") (pintype "input"))
      (node (ref "U17") (pin "7") (pinfunction "VSS_7") (pintype "power_in"))
      (node (ref "U17") (pin "8") (pinfunction "S_8") (pintype "input"))
      (node (ref "U18") (pin "6") (pinfunction "S_6") (pintype "input"))
      (node (ref "U18") (pin "7") (pinfunction "VSS_7") (pintype "power_in"))
      (node (ref "U18") (pin "8") (pinfunction "S_8") (pintype "input"))
      (node (ref "U19") (pin "12") (pinfunction "CCKEN_12") (pintype "input"))
      (node (ref "U19") (pin "14") (pinfunction "G_14") (pintype "input"))
      (node (ref "U19") (pin "8") (pinfunction "GND_8") (pintype "power_in"))
      (node (ref "U2") (pin "1") (pinfunction "GND/ADJ_1") (pintype "power_in"))
      (node (ref "U3") (pin "11") (pinfunction "V-_11") (pintype "power_in"))
      (node (ref "U4") (pin "11") (pinfunction "V-_11") (pintype "power_in"))
      (node (ref "U5") (pin "7") (pinfunction "GND_7") (pintype "power_in"))
      (node (ref "U6") (pin "7") (pinfunction "GND_7") (pintype "power_in"))
      (node (ref "U7") (pin "7") (pinfunction "GND_7") (pintype "power_in"))
      (node (ref "U8") (pin "7") (pinfunction "GND_7") (pintype "power_in"))
      (node (ref "U9") (pin "7") (pinfunction "GND_7") (pintype "power_in"))
      (node (ref "U9") (pin "9") (pinfunction "I1_9") (pintype "input"))
    )
    (net (code "28") (name "H-C") (class "Default")
      (node (ref "U19") (pin "7") (pinfunction "QH_7") (pintype "tri_state"))
    )
    (net (code "29") (name "Net-(D1-PadA)") (class "Default")
      (node (ref "D1") (pin "A") (pinfunction "A_A") (pintype "passive"))
      (node (ref "P1") (pin "1") (pinfunction "1_1") (pintype "bidirectional"))
    )
    (net (code "30") (name "Net-(D2-1)") (class "Default")
      (node (ref "C3") (pin "2") (pinfunction "2_2") (pintype "passive"))
      (node (ref "D2") (pin "A") (pinfunction "1_A") (pintype "bidirectional"))
      (node (ref "R9") (pin "1") (pinfunction "1_1") (pintype "passive"))
      (node (ref "U17") (pin "4") (pinfunction "R_4") (pintype "input"))
    )
    (net (code "31") (name "Net-(D3-1)") (class "Default")
      (node (ref "C4") (pin "2") (pinfunction "2_2") (pintype "passive"))
      (node (ref "D3") (pin "A") (pinfunction "1_A") (pintype "bidirectional"))
      (node (ref "R10") (pin "1") (pinfunction "1_1") (pintype "passive"))
      (node (ref "U17") (pin "10") (pinfunction "R_10") (pintype "input"))
    )
    (net (code "32") (name "Net-(D4-1)") (class "Default")
      (node (ref "C5") (pin "2") (pinfunction "2_2") (pintype "passive"))
      (node (ref "D4") (pin "A") (pinfunction "1_A") (pintype "bidirectional"))
      (node (ref "R11") (pin "1") (pinfunction "1_1") (pintype "passive"))
      (node (ref "U18") (pin "10") (pinfunction "R_10") (pintype "input"))
    )
    (net (code "33") (name "Net-(D5-1)") (class "Default")
      (node (ref "C6") (pin "2") (pinfunction "2_2") (pintype "passive"))
      (node (ref "D5") (pin "A") (pinfunction "1_A") (pintype "bidirectional"))
      (node (ref "R12") (pin "1") (pinfunction "1_1") (pintype "passive"))
      (node (ref "U18") (pin "4") (pinfunction "R_4") (pintype "input"))
    )
    (net (code "34") (name "Net-(D6-1)") (class "Default")
      (node (ref "C7") (pin "2") (pinfunction "2_2") (pintype "passive"))
      (node (ref "D6") (pin "A") (pinfunction "1_A") (pintype "bidirectional"))
      (node (ref "R13") (pin "1") (pinfunction "1_1") (pintype "passive"))
      (node (ref "U16") (pin "4") (pinfunction "R_4") (pintype "input"))
    )
    (net (code "35") (name "Net-(D7-1)") (class "Default")
      (node (ref "C8") (pin "2") (pinfunction "2_2") (pintype "passive"))
      (node (ref "D7") (pin "A") (pinfunction "1_A") (pintype "bidirectional"))
      (node (ref "R14") (pin "1") (pinfunction "1_1") (pintype "passive"))
      (node (ref "U16") (pin "10") (pinfunction "R_10") (pintype "input"))
    )
    (net (code "36") (name "Net-(D10-2)") (class "Default")
      (node (ref "D10") (pin "C") (pinfunction "2_C") (pintype "bidirectional"))
      (node (ref "D11") (pin "C") (pinfunction "2_C") (pintype "bidirectional"))
      (node (ref "D12") (pin "C") (pinfunction "2_C") (pintype "bidirectional"))
      (node (ref "D14") (pin "C") (pinfunction "2_C") (pintype "bidirectional"))
      (node (ref "D8") (pin "C") (pinfunction "2_C") (pintype "bidirectional"))
      (node (ref "D9") (pin "C") (pinfunction "2_C") (pintype "bidirectional"))
      (node (ref "U5") (pin "6") (pinfunction "I1_6") (pintype "input"))
    )
    (net (code "37") (name "Net-(D13-2)") (class "Default")
      (node (ref "D13") (pin "C") (pinfunction "2_C") (pintype "bidirectional"))
      (node (ref "D15") (pin "C") (pinfunction "2_C") (pintype "bidirectional"))
      (node (ref "D16") (pin "C") (pinfunction "2_C") (pintype "bidirectional"))
      (node (ref "D17") (pin "C") (pinfunction "2_C") (pintype "bidirectional"))
      (node (ref "D18") (pin "C") (pinfunction "2_C") (pintype "bidirectional"))
      (node (ref "D19") (pin "C") (pinfunction "2_C") (pintype "bidirectional"))
      (node (ref "U7") (pin "12") (pinfunction "I1_12") (pintype "input"))
    )
    (net (code "38") (name "Net-(D20-2)") (class "Default")
      (node (ref "D20") (pin "C") (pinfunction "2_C") (pintype "bidirectional"))
      (node (ref "D21") (pin "C") (pinfunction "2_C") (pintype "bidirectional"))
      (node (ref "D22") (pin "C") (pinfunction "2_C") (pintype "bidirectional"))
      (node (ref "D23") (pin "C") (pinfunction "2_C") (pintype "bidirectional"))
      (node (ref "D24") (pin "C") (pinfunction "2_C") (pintype "bidirectional"))
      (node (ref "D25") (pin "C") (pinfunction "2_C") (pintype "bidirectional"))
      (node (ref "U6") (pin "6") (pinfunction "I1_6") (pintype "input"))
    )
    (net (code "39") (name "Net-(D26-2)") (class "Default")
      (node (ref "D26") (pin "C") (pinfunction "2_C") (pintype "bidirectional"))
      (node (ref "D27") (pin "C") (pinfunction "2_C") (pintype "bidirectional"))
      (node (ref "D28") (pin "C") (pinfunction "2_C") (pintype "bidirectional"))
      (node (ref "D29") (pin "C") (pinfunction "2_C") (pintype "bidirectional"))
      (node (ref "D30") (pin "C") (pinfunction "2_C") (pintype "bidirectional"))
      (node (ref "D31") (pin "C") (pinfunction "2_C") (pintype "bidirectional"))
      (node (ref "U6") (pin "12") (pinfunction "I1_12") (pintype "input"))
    )
    (net (code "40") (name "Net-(D32-2)") (class "Default")
      (node (ref "D32") (pin "C") (pinfunction "2_C") (pintype "bidirectional"))
      (node (ref "D33") (pin "C") (pinfunction "2_C") (pintype "bidirectional"))
      (node (ref "D34") (pin "C") (pinfunction "2_C") (pintype "bidirectional"))
      (node (ref "D35") (pin "C") (pinfunction "2_C") (pintype "bidirectional"))
      (node (ref "D36") (pin "C") (pinfunction "2_C") (pintype "bidirectional"))
      (node (ref "D37") (pin "C") (pinfunction "2_C") (pintype "bidirectional"))
      (node (ref "U7") (pin "6") (pinfunction "I1_6") (pintype "input"))
    )
    (net (code "41") (name "Net-(D38-2)") (class "Default")
      (node (ref "D38") (pin "C") (pinfunction "2_C") (pintype "bidirectional"))
      (node (ref "D39") (pin "C") (pinfunction "2_C") (pintype "bidirectional"))
      (node (ref "D40") (pin "C") (pinfunction "2_C") (pintype "bidirectional"))
      (node (ref "D41") (pin "C") (pinfunction "2_C") (pintype "bidirectional"))
      (node (ref "D42") (pin "C") (pinfunction "2_C") (pintype "bidirectional"))
      (node (ref "D43") (pin "C") (pinfunction "2_C") (pintype "bidirectional"))
      (node (ref "U5") (pin "12") (pinfunction "I1_12") (pintype "input"))
    )
    (net (code "42") (name "Net-(D44-1)") (class "Default")
      (node (ref "D44") (pin "A") (pinfunction "1_A") (pintype "bidirectional"))
      (node (ref "U10") (pin "3") (pinfunction "O_3") (pintype "open_collector"))
    )
    (net (code "43") (name "Net-(D45-1)") (class "Default")
      (node (ref "D45") (pin "A") (pinfunction "1_A") (pintype "bidirectional"))
      (node (ref "U10") (pin "6") (pinfunction "O_6") (pintype "open_collector"))
    )
    (net (code "44") (name "Net-(D46-1)") (class "Default")
      (node (ref "D46") (pin "A") (pinfunction "1_A") (pintype "bidirectional"))
      (node (ref "U10") (pin "8") (pinfunction "O_8") (pintype "open_collector"))
    )
    (net (code "45") (name "Net-(D47-1)") (class "Default")
      (node (ref "D47") (pin "A") (pinfunction "1_A") (pintype "bidirectional"))
      (node (ref "D56") (pin "A") (pinfunction "1_A") (pintype "bidirectional"))
      (node (ref "U6") (pin "1") (pinfunction "O_1") (pintype "output"))
      (node (ref "U6") (pin "5") (pinfunction "I0_5") (pintype "input"))
    )
    (net (code "46") (name "Net-(D53-1)") (class "Default")
      (node (ref "D53") (pin "A") (pinfunction "1_A") (pintype "bidirectional"))
      (node (ref "D59") (pin "A") (pinfunction "1_A") (pintype "bidirectional"))
      (node (ref "U6") (pin "10") (pinfunction "O_10") (pintype "output"))
      (node (ref "U6") (pin "11") (pinfunction "I0_11") (pintype "input"))
    )
    (net (code "47") (name "Net-(D54-1)") (class "Default")
      (node (ref "D54") (pin "A") (pinfunction "1_A") (pintype "bidirectional"))
      (node (ref "U5") (pin "1") (pinfunction "O_1") (pintype "output"))
      (node (ref "U5") (pin "5") (pinfunction "I0_5") (pintype "input"))
    )
    (net (code "48") (name "Net-(D55-1)") (class "Default")
      (node (ref "D55") (pin "A") (pinfunction "1_A") (pintype "bidirectional"))
      (node (ref "D60") (pin "A") (pinfunction "1_A") (pintype "bidirectional"))
      (node (ref "U5") (pin "10") (pinfunction "O_10") (pintype "output"))
      (node (ref "U7") (pin "11") (pinfunction "I0_11") (pintype "input"))
    )
    (net (code "49") (name "Net-(D58-1)") (class "Default")
      (node (ref "D58") (pin "A") (pinfunction "1_A") (pintype "bidirectional"))
      (node (ref "D65") (pin "A") (pinfunction "1_A") (pintype "bidirectional"))
      (node (ref "U7") (pin "1") (pinfunction "O_1") (pintype "output"))
      (node (ref "U7") (pin "5") (pinfunction "I0_5") (pintype "input"))
    )
    (net (code "50") (name "Net-(D64-1)") (class "Default")
      (node (ref "D64") (pin "A") (pinfunction "1_A") (pintype "bidirectional"))
      (node (ref "R20") (pin "2") (pinfunction "2_2") (pintype "passive"))
    )
    (net (code "51") (name "Net-(D66-1)") (class "Default")
      (node (ref "D66") (pin "A") (pinfunction "1_A") (pintype "bidirectional"))
      (node (ref "R21") (pin "2") (pinfunction "2_2") (pintype "passive"))
    )
    (net (code "52") (name "Net-(D67-1)") (class "Default")
      (node (ref "D67") (pin "A") (pinfunction "1_A") (pintype "bidirectional"))
      (node (ref "R22") (pin "2") (pinfunction "2_2") (pintype "passive"))
    )
    (net (code "53") (name "Net-(LED1-PadA)") (class "Default")
      (node (ref "LED1") (pin "A") (pinfunction "A_A") (pintype "passive"))
      (node (ref "R29") (pin "2") (pinfunction "2_2") (pintype "passive"))
    )
    (net (code "54") (name "Net-(LED2-PadA)") (class "Default")
      (node (ref "LED2") (pin "A") (pinfunction "A_A") (pintype "passive"))
      (node (ref "R23") (pin "2") (pinfunction "2_2") (pintype "passive"))
    )
    (net (code "55") (name "Net-(LED3-PadA)") (class "Default")
      (node (ref "LED3") (pin "A") (pinfunction "A_A") (pintype "passive"))
      (node (ref "R24") (pin "2") (pinfunction "2_2") (pintype "passive"))
    )
    (net (code "56") (name "Net-(LED4-PadA)") (class "Default")
      (node (ref "LED4") (pin "A") (pinfunction "A_A") (pintype "passive"))
      (node (ref "R25") (pin "2") (pinfunction "2_2") (pintype "passive"))
    )
    (net (code "57") (name "Net-(LED5-PadA)") (class "Default")
      (node (ref "LED5") (pin "A") (pinfunction "A_A") (pintype "passive"))
      (node (ref "R26") (pin "2") (pinfunction "2_2") (pintype "passive"))
    )
    (net (code "58") (name "Net-(LED6-PadA)") (class "Default")
      (node (ref "LED6") (pin "A") (pinfunction "A_A") (pintype "passive"))
      (node (ref "R27") (pin "2") (pinfunction "2_2") (pintype "passive"))
    )
    (net (code "59") (name "Net-(T1-C)") (class "Default")
      (node (ref "D63") (pin "2") (pinfunction "2_2") (pintype "bidirectional"))
      (node (ref "T1") (pin "2") (pinfunction "C_2") (pintype "passive"))
      (node (ref "X1") (pin "2") (pinfunction "S_2") (pintype "passive"))
    )
    (net (code "60") (name "Net-(U1-DIS)") (class "Default")
      (node (ref "C9") (pin "1") (pinfunction "1_1") (pintype "passive"))
      (node (ref "R16") (pin "1") (pinfunction "1_1") (pintype "passive"))
      (node (ref "U1") (pin "2") (pinfunction "TRI_2") (pintype "input"))
      (node (ref "U1") (pin "7") (pinfunction "DIS_7") (pintype "input"))
    )
    (net (code "61") (name "Net-(U1-TRE)") (class "Default")
      (node (ref "R15") (pin "1") (pinfunction "1_1") (pintype "passive"))
      (node (ref "R16") (pin "2") (pinfunction "2_2") (pintype "passive"))
      (node (ref "U1") (pin "6") (pinfunction "TRE_6") (pintype "input"))
    )
    (net (code "62") (name "Net-(U2-VIN)") (class "Default")
      (node (ref "C2") (pin "+") (pinfunction "+_+") (pintype "passive"))
      (node (ref "D1") (pin "C") (pinfunction "C_C") (pintype "passive"))
      (node (ref "U2") (pin "3") (pinfunction "VIN_3") (pintype "input"))
    )
    (net (code "63") (name "Net-(U3A-+IN)") (class "Default")
      (node (ref "R1") (pin "1") (pinfunction "1_1") (pintype "passive"))
      (node (ref "R2") (pin "2") (pinfunction "2_2") (pintype "passive"))
      (node (ref "U3") (pin "3") (pinfunction "+IN_3") (pintype "input"))
    )
    (net (code "64") (name "Net-(U3B-+IN)") (class "Default")
      (node (ref "R2") (pin "1") (pinfunction "1_1") (pintype "passive"))
      (node (ref "R3") (pin "2") (pinfunction "2_2") (pintype "passive"))
      (node (ref "U3") (pin "5") (pinfunction "+IN_5") (pintype "input"))
    )
    (net (code "65") (name "Net-(U3C-+IN)") (class "Default")
      (node (ref "R3") (pin "1") (pinfunction "1_1") (pintype "passive"))
      (node (ref "R4") (pin "2") (pinfunction "2_2") (pintype "passive"))
      (node (ref "U3") (pin "10") (pinfunction "+IN_10") (pintype "input"))
    )
    (net (code "66") (name "Net-(U3D-+IN)") (class "Default")
      (node (ref "R4") (pin "1") (pinfunction "1_1") (pintype "passive"))
      (node (ref "R5") (pin "2") (pinfunction "2_2") (pintype "passive"))
      (node (ref "U3") (pin "12") (pinfunction "+IN_12") (pintype "input"))
    )
    (net (code "67") (name "Net-(U4A-+IN)") (class "Default")
      (node (ref "R5") (pin "1") (pinfunction "1_1") (pintype "passive"))
      (node (ref "R6") (pin "2") (pinfunction "2_2") (pintype "passive"))
      (node (ref "U4") (pin "3") (pinfunction "+IN_3") (pintype "input"))
    )
    (net (code "68") (name "Net-(U4B-+IN)") (class "Default")
      (node (ref "R6") (pin "1") (pinfunction "1_1") (pintype "passive"))
      (node (ref "R7") (pin "2") (pinfunction "2_2") (pintype "passive"))
      (node (ref "U4") (pin "5") (pinfunction "+IN_5") (pintype "input"))
    )
    (net (code "69") (name "Net-(U5A-I1)") (class "Default")
      (node (ref "U5") (pin "3") (pinfunction "I1_3") (pintype "input"))
      (node (ref "U5") (pin "4") (pinfunction "O_4") (pintype "output"))
    )
    (net (code "70") (name "Net-(U5C-I1)") (class "Default")
      (node (ref "U5") (pin "9") (pinfunction "I1_9") (pintype "input"))
      (node (ref "U7") (pin "13") (pinfunction "O_13") (pintype "output"))
    )
    (net (code "71") (name "Net-(U5D-O)") (class "Default")
      (node (ref "U5") (pin "13") (pinfunction "O_13") (pintype "output"))
      (node (ref "U7") (pin "9") (pinfunction "I1_9") (pintype "input"))
    )
    (net (code "72") (name "Net-(U6A-I1)") (class "Default")
      (node (ref "U6") (pin "3") (pinfunction "I1_3") (pintype "input"))
      (node (ref "U6") (pin "4") (pinfunction "O_4") (pintype "output"))
    )
    (net (code "73") (name "Net-(U6C-I1)") (class "Default")
      (node (ref "U6") (pin "13") (pinfunction "O_13") (pintype "output"))
      (node (ref "U6") (pin "9") (pinfunction "I1_9") (pintype "input"))
    )
    (net (code "74") (name "Net-(U7A-I1)") (class "Default")
      (node (ref "U7") (pin "3") (pinfunction "I1_3") (pintype "input"))
      (node (ref "U7") (pin "4") (pinfunction "O_4") (pintype "output"))
    )
    (net (code "75") (name "Net-(U8A-I1)") (class "Default")
      (node (ref "U8") (pin "3") (pinfunction "I1_3") (pintype "input"))
      (node (ref "U8") (pin "4") (pinfunction "O_4") (pintype "output"))
    )
    (net (code "76") (name "Net-(U8C-I1)") (class "Default")
      (node (ref "U8") (pin "13") (pinfunction "O_13") (pintype "output"))
      (node (ref "U8") (pin "9") (pinfunction "I1_9") (pintype "input"))
    )
    (net (code "77") (name "Net-(U9A-I1)") (class "Default")
      (node (ref "U9") (pin "3") (pinfunction "I1_3") (pintype "input"))
      (node (ref "U9") (pin "4") (pinfunction "O_4") (pintype "output"))
    )
    (net (code "78") (name "Net-(U10D-O)") (class "Default")
      (node (ref "R20") (pin "1") (pinfunction "1_1") (pintype "passive"))
      (node (ref "U10") (pin "11") (pinfunction "O_11") (pintype "open_collector"))
    )
    (net (code "79") (name "Net-(U11A-O)") (class "Default")
      (node (ref "R21") (pin "1") (pinfunction "1_1") (pintype "passive"))
      (node (ref "U11") (pin "3") (pinfunction "O_3") (pintype "open_collector"))
    )
    (net (code "80") (name "Net-(U11B-O)") (class "Default")
      (node (ref "R22") (pin "1") (pinfunction "1_1") (pintype "passive"))
      (node (ref "U11") (pin "6") (pinfunction "O_6") (pintype "open_collector"))
    )
    (net (code "81") (name "Net-(U12A-I0)") (class "Default")
      (node (ref "U12") (pin "1") (pinfunction "I0_1") (pintype "input"))
      (node (ref "U12") (pin "6") (pinfunction "O_6") (pintype "open_collector"))
    )
    (net (code "82") (name "Net-(U12C-I0)") (class "Default")
      (node (ref "U12") (pin "11") (pinfunction "O_11") (pintype "open_collector"))
      (node (ref "U12") (pin "9") (pinfunction "I0_9") (pintype "input"))
    )
    (net (code "83") (name "Net-(U13A-I0)") (class "Default")
      (node (ref "U13") (pin "1") (pinfunction "I0_1") (pintype "input"))
      (node (ref "U13") (pin "8") (pinfunction "O_8") (pintype "open_collector"))
    )
    (net (code "84") (name "Net-(U13B-I0)") (class "Default")
      (node (ref "U13") (pin "11") (pinfunction "O_11") (pintype "open_collector"))
      (node (ref "U13") (pin "4") (pinfunction "I0_4") (pintype "input"))
    )
    (net (code "85") (name "Net-(U14A-I0)") (class "Default")
      (node (ref "U14") (pin "1") (pinfunction "I0_1") (pintype "input"))
      (node (ref "U3") (pin "1") (pinfunction "OUT_1") (pintype "output"))
    )
    (net (code "86") (name "Net-(U14A-I1)") (class "Default")
      (node (ref "U14") (pin "2") (pinfunction "I1_2") (pintype "input"))
      (node (ref "U14") (pin "4") (pinfunction "I0_4") (pintype "input"))
      (node (ref "U3") (pin "7") (pinfunction "OUT_7") (pintype "output"))
    )
    (net (code "87") (name "Net-(U14B-I1)") (class "Default")
      (node (ref "U14") (pin "5") (pinfunction "I1_5") (pintype "input"))
      (node (ref "U14") (pin "9") (pinfunction "I0_9") (pintype "input"))
      (node (ref "U3") (pin "8") (pinfunction "OUT_8") (pintype "output"))
    )
    (net (code "88") (name "Net-(U14C-I1)") (class "Default")
      (node (ref "U14") (pin "10") (pinfunction "I1_10") (pintype "input"))
      (node (ref "U14") (pin "12") (pinfunction "I0_12") (pintype "input"))
      (node (ref "U3") (pin "14") (pinfunction "OUT_14") (pintype "output"))
    )
    (net (code "89") (name "Net-(U14D-I1)") (class "Default")
      (node (ref "U14") (pin "13") (pinfunction "I1_13") (pintype "input"))
      (node (ref "U15") (pin "1") (pinfunction "I0_1") (pintype "input"))
      (node (ref "U4") (pin "1") (pinfunction "OUT_1") (pintype "output"))
    )
    (net (code "90") (name "Net-(U15A-I1)") (class "Default")
      (node (ref "U15") (pin "2") (pinfunction "I1_2") (pintype "input"))
      (node (ref "U15") (pin "4") (pinfunction "I0_4") (pintype "input"))
      (node (ref "U4") (pin "7") (pinfunction "OUT_7") (pintype "output"))
    )
    (net (code "91") (name "OFF") (class "Default")
      (node (ref "D14") (pin "A") (pinfunction "1_A") (pintype "bidirectional"))
    )
    (net (code "92") (name "OFF_SR") (class "Default")
      (node (ref "D54") (pin "C") (pinfunction "2_C") (pintype "bidirectional"))
      (node (ref "U9") (pin "8") (pinfunction "I0_8") (pintype "input"))
    )
    (net (code "93") (name "ON") (class "Default")
      (node (ref "D43") (pin "A") (pinfunction "1_A") (pintype "bidirectional"))
    )
    (net (code "94") (name "ON_SR_LATCH") (class "Default")
      (node (ref "D48") (pin "A") (pinfunction "1_A") (pintype "bidirectional"))
      (node (ref "U5") (pin "11") (pinfunction "I0_11") (pintype "input"))
      (node (ref "U7") (pin "10") (pinfunction "O_10") (pintype "output"))
    )
    (net (code "95") (name "RESET_SW_SR") (class "Default")
      (node (ref "C10") (pin "1") (pinfunction "1_1") (pintype "passive"))
      (node (ref "D44") (pin "C") (pinfunction "2_C") (pintype "bidirectional"))
      (node (ref "D45") (pin "C") (pinfunction "2_C") (pintype "bidirectional"))
      (node (ref "D46") (pin "C") (pinfunction "2_C") (pintype "bidirectional"))
      (node (ref "D68") (pin "C") (pinfunction "2_C") (pintype "bidirectional"))
      (node (ref "D69") (pin "C") (pinfunction "2_C") (pintype "bidirectional"))
      (node (ref "D70") (pin "C") (pinfunction "2_C") (pintype "bidirectional"))
      (node (ref "D71") (pin "C") (pinfunction "2_C") (pintype "bidirectional"))
      (node (ref "D72") (pin "C") (pinfunction "2_C") (pintype "bidirectional"))
      (node (ref "D73") (pin "C") (pinfunction "2_C") (pintype "bidirectional"))
      (node (ref "U19") (pin "10") (pinfunction "CCLR_10") (pintype "input"))
      (node (ref "U8") (pin "12") (pinfunction "I1_12") (pintype "input"))
      (node (ref "U8") (pin "6") (pinfunction "I1_6") (pintype "input"))
      (node (ref "U9") (pin "6") (pinfunction "I1_6") (pintype "input"))
    )
    (net (code "96") (name "SR_25") (class "Default")
      (node (ref "D60") (pin "C") (pinfunction "2_C") (pintype "bidirectional"))
      (node (ref "U10") (pin "2") (pinfunction "I1_2") (pintype "input"))
    )
    (net (code "97") (name "SR_50") (class "Default")
      (node (ref "D47") (pin "C") (pinfunction "2_C") (pintype "bidirectional"))
      (node (ref "U10") (pin "5") (pinfunction "I1_5") (pintype "input"))
    )
    (net (code "98") (name "SR_75") (class "Default")
      (node (ref "D53") (pin "C") (pinfunction "2_C") (pintype "bidirectional"))
      (node (ref "U10") (pin "10") (pinfunction "I1_10") (pintype "input"))
    )
    (net (code "99") (name "SR_100") (class "Default")
      (node (ref "D65") (pin "C") (pinfunction "2_C") (pintype "bidirectional"))
    )
    (net (code "100") (name "SR_DRIVER_1") (class "Default")
      (node (ref "D70") (pin "A") (pinfunction "1_A") (pintype "bidirectional"))
      (node (ref "D72") (pin "A") (pinfunction "1_A") (pintype "bidirectional"))
    )
    (net (code "101") (name "SR_DRIVER_2") (class "Default")
      (node (ref "D68") (pin "A") (pinfunction "1_A") (pintype "bidirectional"))
      (node (ref "D73") (pin "A") (pinfunction "1_A") (pintype "bidirectional"))
    )
    (net (code "102") (name "SR_DRIVER_3") (class "Default")
      (node (ref "D69") (pin "A") (pinfunction "1_A") (pintype "bidirectional"))
      (node (ref "D71") (pin "A") (pinfunction "1_A") (pintype "bidirectional"))
    )
    (net (code "103") (name "SR_SW1") (class "Default")
      (node (ref "U10") (pin "12") (pinfunction "I0_12") (pintype "input"))
      (node (ref "U8") (pin "1") (pinfunction "O_1") (pintype "output"))
      (node (ref "U8") (pin "5") (pinfunction "I0_5") (pintype "input"))
    )
    (net (code "104") (name "SR_SW2") (class "Default")
      (node (ref "U11") (pin "1") (pinfunction "I0_1") (pintype "input"))
      (node (ref "U8") (pin "10") (pinfunction "O_10") (pintype "output"))
      (node (ref "U8") (pin "11") (pinfunction "I0_11") (pintype "input"))
    )
    (net (code "105") (name "SR_SW3") (class "Default")
      (node (ref "U11") (pin "4") (pinfunction "I0_4") (pintype "input"))
      (node (ref "U9") (pin "1") (pinfunction "O_1") (pintype "output"))
      (node (ref "U9") (pin "5") (pinfunction "I0_5") (pintype "input"))
    )
    (net (code "106") (name "SW1") (class "Default")
      (node (ref "C13") (pin "1") (pinfunction "1_1") (pintype "passive"))
      (node (ref "R17") (pin "2") (pinfunction "2_2") (pintype "passive"))
      (node (ref "SW1") (pin "1") (pinfunction "1_1") (pintype "bidirectional"))
      (node (ref "SW1") (pin "2") (pinfunction "1_2") (pintype "bidirectional"))
      (node (ref "U8") (pin "2") (pinfunction "I0_2") (pintype "input"))
    )
    (net (code "107") (name "SW2") (class "Default")
      (node (ref "C12") (pin "1") (pinfunction "1_1") (pintype "passive"))
      (node (ref "R18") (pin "2") (pinfunction "2_2") (pintype "passive"))
      (node (ref "SW2") (pin "1") (pinfunction "1_1") (pintype "bidirectional"))
      (node (ref "SW2") (pin "2") (pinfunction "1_2") (pintype "bidirectional"))
      (node (ref "U8") (pin "8") (pinfunction "I0_8") (pintype "input"))
    )
    (net (code "108") (name "SW3") (class "Default")
      (node (ref "C11") (pin "1") (pinfunction "1_1") (pintype "passive"))
      (node (ref "D48") (pin "C") (pinfunction "2_C") (pintype "bidirectional"))
      (node (ref "R19") (pin "2") (pinfunction "2_2") (pintype "passive"))
      (node (ref "SW3") (pin "1") (pinfunction "1_1") (pintype "bidirectional"))
      (node (ref "SW3") (pin "2") (pinfunction "1_2") (pintype "bidirectional"))
      (node (ref "U9") (pin "2") (pinfunction "I0_2") (pintype "input"))
    )
    (net (code "109") (name "VCC") (class "Default")
      (node (ref "C1") (pin "+") (pinfunction "+_+") (pintype "passive"))
      (node (ref "C14") (pin "1") (pinfunction "1_1") (pintype "passive"))
      (node (ref "C15") (pin "1") (pinfunction "1_1") (pintype "passive"))
      (node (ref "C16") (pin "1") (pinfunction "1_1") (pintype "passive"))
      (node (ref "C17") (pin "1") (pinfunction "1_1") (pintype "passive"))
      (node (ref "C18") (pin "1") (pinfunction "1_1") (pintype "passive"))
      (node (ref "C19") (pin "1") (pinfunction "1_1") (pintype "passive"))
      (node (ref "C20") (pin "1") (pinfunction "1_1") (pintype "passive"))
      (node (ref "C21") (pin "1") (pinfunction "1_1") (pintype "passive"))
      (node (ref "C22") (pin "1") (pinfunction "1_1") (pintype "passive"))
      (node (ref "C23") (pin "1") (pinfunction "1_1") (pintype "passive"))
      (node (ref "C24") (pin "1") (pinfunction "1_1") (pintype "passive"))
      (node (ref "C25") (pin "1") (pinfunction "1_1") (pintype "passive"))
      (node (ref "C26") (pin "1") (pinfunction "1_1") (pintype "passive"))
      (node (ref "C27") (pin "1") (pinfunction "1_1") (pintype "passive"))
      (node (ref "C28") (pin "1") (pinfunction "1_1") (pintype "passive"))
      (node (ref "C29") (pin "1") (pinfunction "1_1") (pintype "passive"))
      (node (ref "C30") (pin "1") (pinfunction "1_1") (pintype "passive"))
      (node (ref "C31") (pin "1") (pinfunction "1_1") (pintype "passive"))
      (node (ref "C32") (pin "1") (pinfunction "1_1") (pintype "passive"))
      (node (ref "R1") (pin "2") (pinfunction "2_2") (pintype "passive"))
      (node (ref "R15") (pin "2") (pinfunction "2_2") (pintype "passive"))
      (node (ref "R8") (pin "A") (pinfunction "A_A") (pintype "passive"))
      (node (ref "SW1") (pin "3") (pinfunction "2_3") (pintype "bidirectional"))
      (node (ref "SW1") (pin "4") (pinfunction "2_4") (pintype "bidirectional"))
      (node (ref "SW2") (pin "3") (pinfunction "2_3") (pintype "bidirectional"))
      (node (ref "SW2") (pin "4") (pinfunction "2_4") (pintype "bidirectional"))
      (node (ref "SW3") (pin "3") (pinfunction "2_3") (pintype "bidirectional"))
      (node (ref "SW3") (pin "4") (pinfunction "2_4") (pintype "bidirectional"))
      (node (ref "U1") (pin "8") (pinfunction "VCC+_8") (pintype "power_in"))
      (node (ref "U10") (pin "14") (pinfunction "VCC_14") (pintype "power_in"))
      (node (ref "U11") (pin "14") (pinfunction "VCC_14") (pintype "power_in"))
      (node (ref "U12") (pin "14") (pinfunction "VCC_14") (pintype "power_in"))
      (node (ref "U13") (pin "14") (pinfunction "VCC_14") (pintype "power_in"))
      (node (ref "U14") (pin "14") (pinfunction "VCC_14") (pintype "power_in"))
      (node (ref "U15") (pin "14") (pinfunction "VCC_14") (pintype "power_in"))
      (node (ref "U16") (pin "14") (pinfunction "VDD_14") (pintype "power_in"))
      (node (ref "U16") (pin "5") (pinfunction "D_5") (pintype "input"))
      (node (ref "U16") (pin "9") (pinfunction "D_9") (pintype "input"))
      (node (ref "U17") (pin "14") (pinfunction "VDD_14") (pintype "power_in"))
      (node (ref "U17") (pin "5") (pinfunction "D_5") (pintype "input"))
      (node (ref "U17") (pin "9") (pinfunction "D_9") (pintype "input"))
      (node (ref "U18") (pin "14") (pinfunction "VDD_14") (pintype "power_in"))
      (node (ref "U18") (pin "5") (pinfunction "D_5") (pintype "input"))
      (node (ref "U18") (pin "9") (pinfunction "D_9") (pintype "input"))
      (node (ref "U19") (pin "16") (pinfunction "VCC_16") (pintype "power_in"))
      (node (ref "U2") (pin "2") (pinfunction "VOUT_2") (pintype "output"))
      (node (ref "U3") (pin "4") (pinfunction "V+_4") (pintype "power_in"))
      (node (ref "U4") (pin "4") (pinfunction "V+_4") (pintype "power_in"))
      (node (ref "U5") (pin "14") (pinfunction "VCC_14") (pintype "power_in"))
      (node (ref "U6") (pin "14") (pinfunction "VCC_14") (pintype "power_in"))
      (node (ref "U7") (pin "14") (pinfunction "VCC_14") (pintype "power_in"))
      (node (ref "U8") (pin "14") (pinfunction "VCC_14") (pintype "power_in"))
      (node (ref "U9") (pin "14") (pinfunction "VCC_14") (pintype "power_in"))
      (node (ref "X1") (pin "1") (pinfunction "S_1") (pintype "passive"))
    )
    (net (code "110") (name "unconnected-(U1-CON-Pad5)") (class "Default")
      (node (ref "U1") (pin "5") (pinfunction "CON_5") (pintype "input"))
    )
    (net (code "111") (name "unconnected-(U16A-~{Q}-Pad2)") (class "Default")
      (node (ref "U16") (pin "2") (pinfunction "~{Q}_2") (pintype "output"))
    )
    (net (code "112") (name "unconnected-(U16B-~{Q}-Pad12)") (class "Default")
      (node (ref "U16") (pin "12") (pinfunction "~{Q}_12") (pintype "output"))
    )
    (net (code "113") (name "unconnected-(U17A-~{Q}-Pad2)") (class "Default")
      (node (ref "U17") (pin "2") (pinfunction "~{Q}_2") (pintype "output"))
    )
    (net (code "114") (name "unconnected-(U17B-~{Q}-Pad12)") (class "Default")
      (node (ref "U17") (pin "12") (pinfunction "~{Q}_12") (pintype "output"))
    )
    (net (code "115") (name "unconnected-(U18A-~{Q}-Pad2)") (class "Default")
      (node (ref "U18") (pin "2") (pinfunction "~{Q}_2") (pintype "output"))
    )
    (net (code "116") (name "unconnected-(U18B-~{Q}-Pad12)") (class "Default")
      (node (ref "U18") (pin "12") (pinfunction "~{Q}_12") (pintype "output"))
    )
    (net (code "117") (name "unconnected-(U19A-RCO-Pad9)") (class "Default")
      (node (ref "U19") (pin "9") (pinfunction "RCO_9") (pintype "output"))
    )
    (net (code "118") (name "~{OFF_SR}") (class "Default")
      (node (ref "U10") (pin "13") (pinfunction "I1_13") (pintype "input"))
      (node (ref "U11") (pin "2") (pinfunction "I1_2") (pintype "input"))
      (node (ref "U11") (pin "5") (pinfunction "I1_5") (pintype "input"))
      (node (ref "U9") (pin "10") (pinfunction "O_10") (pintype "output"))
    )
  )
)
